# DDR3_LoongSon.net
KiCad netlist of a schematic drawn in Altium Designer
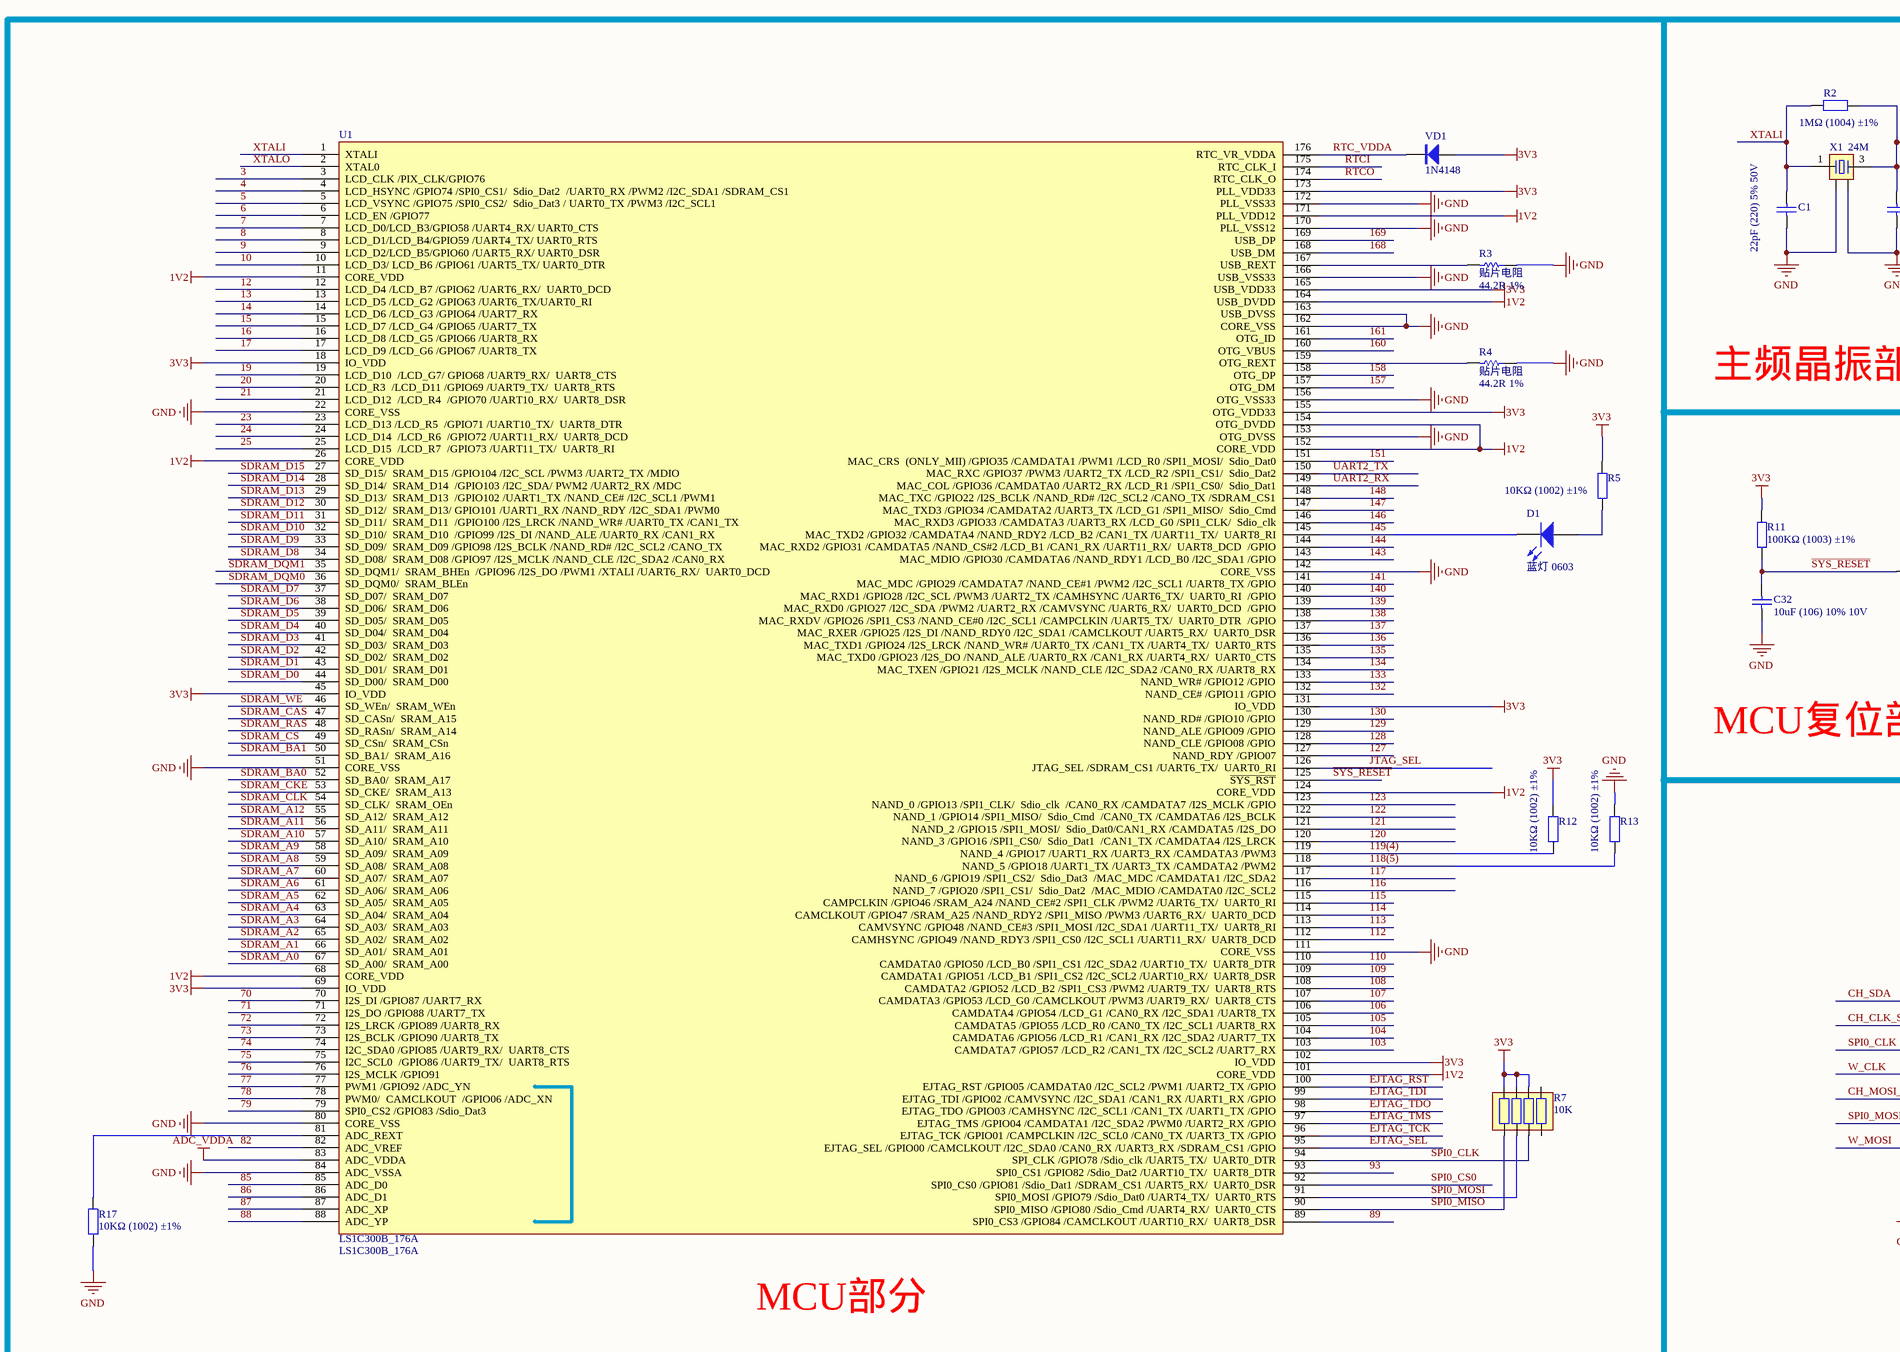
[diagram p0: DDR3_LoongSon.SchDoc, top left]
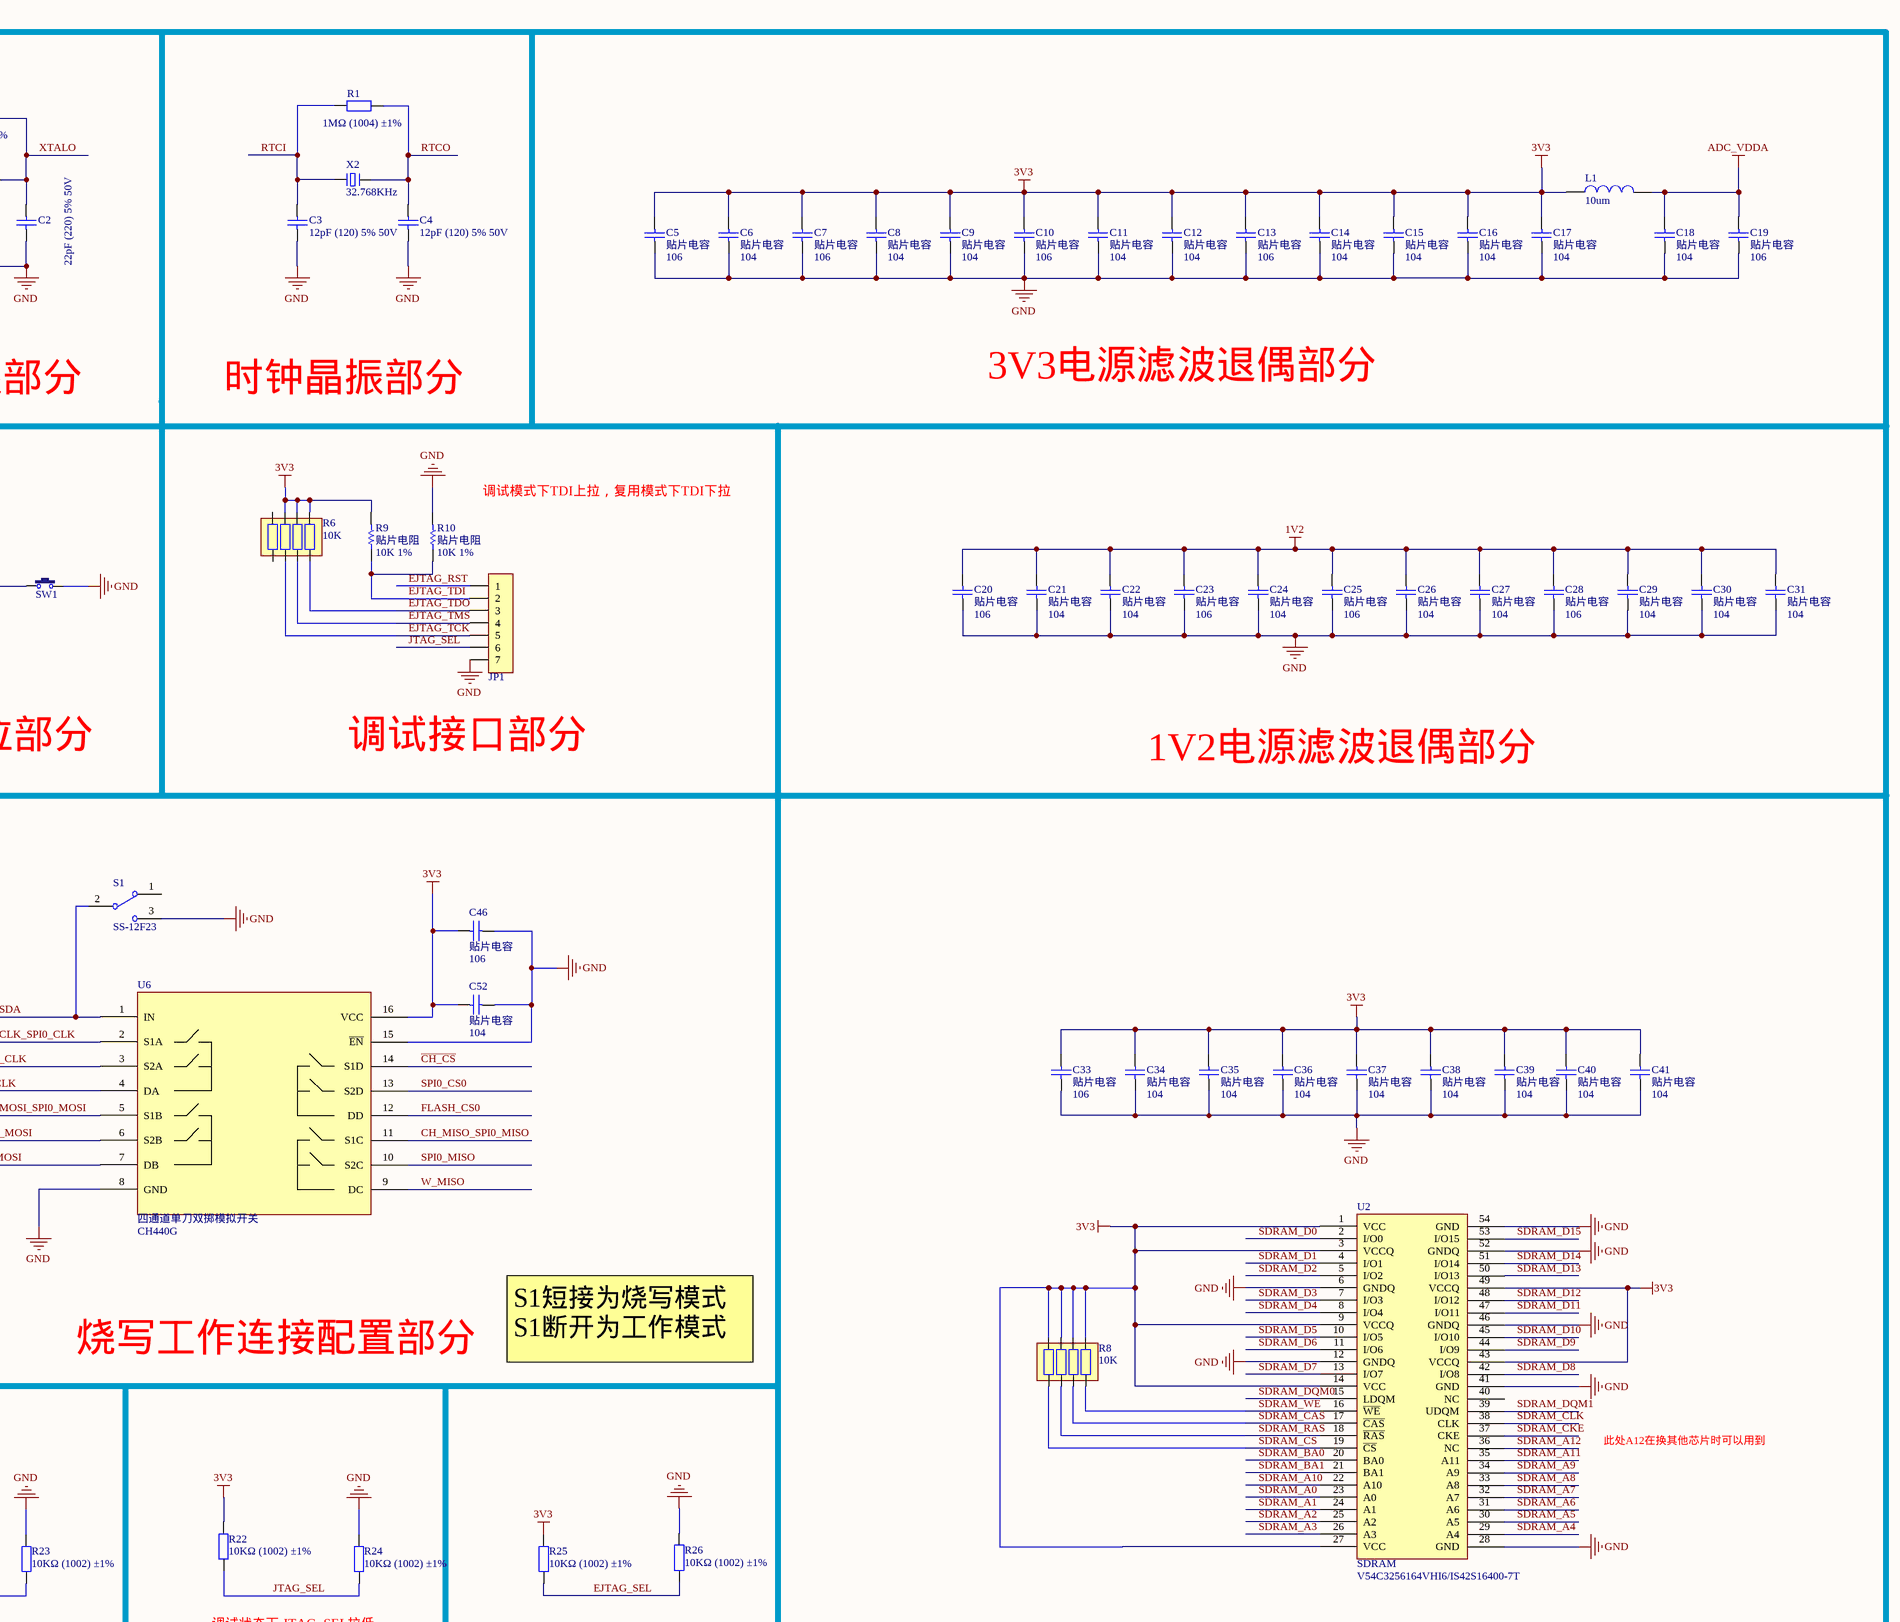
[diagram p1: DDR3_LoongSon.SchDoc, top right]
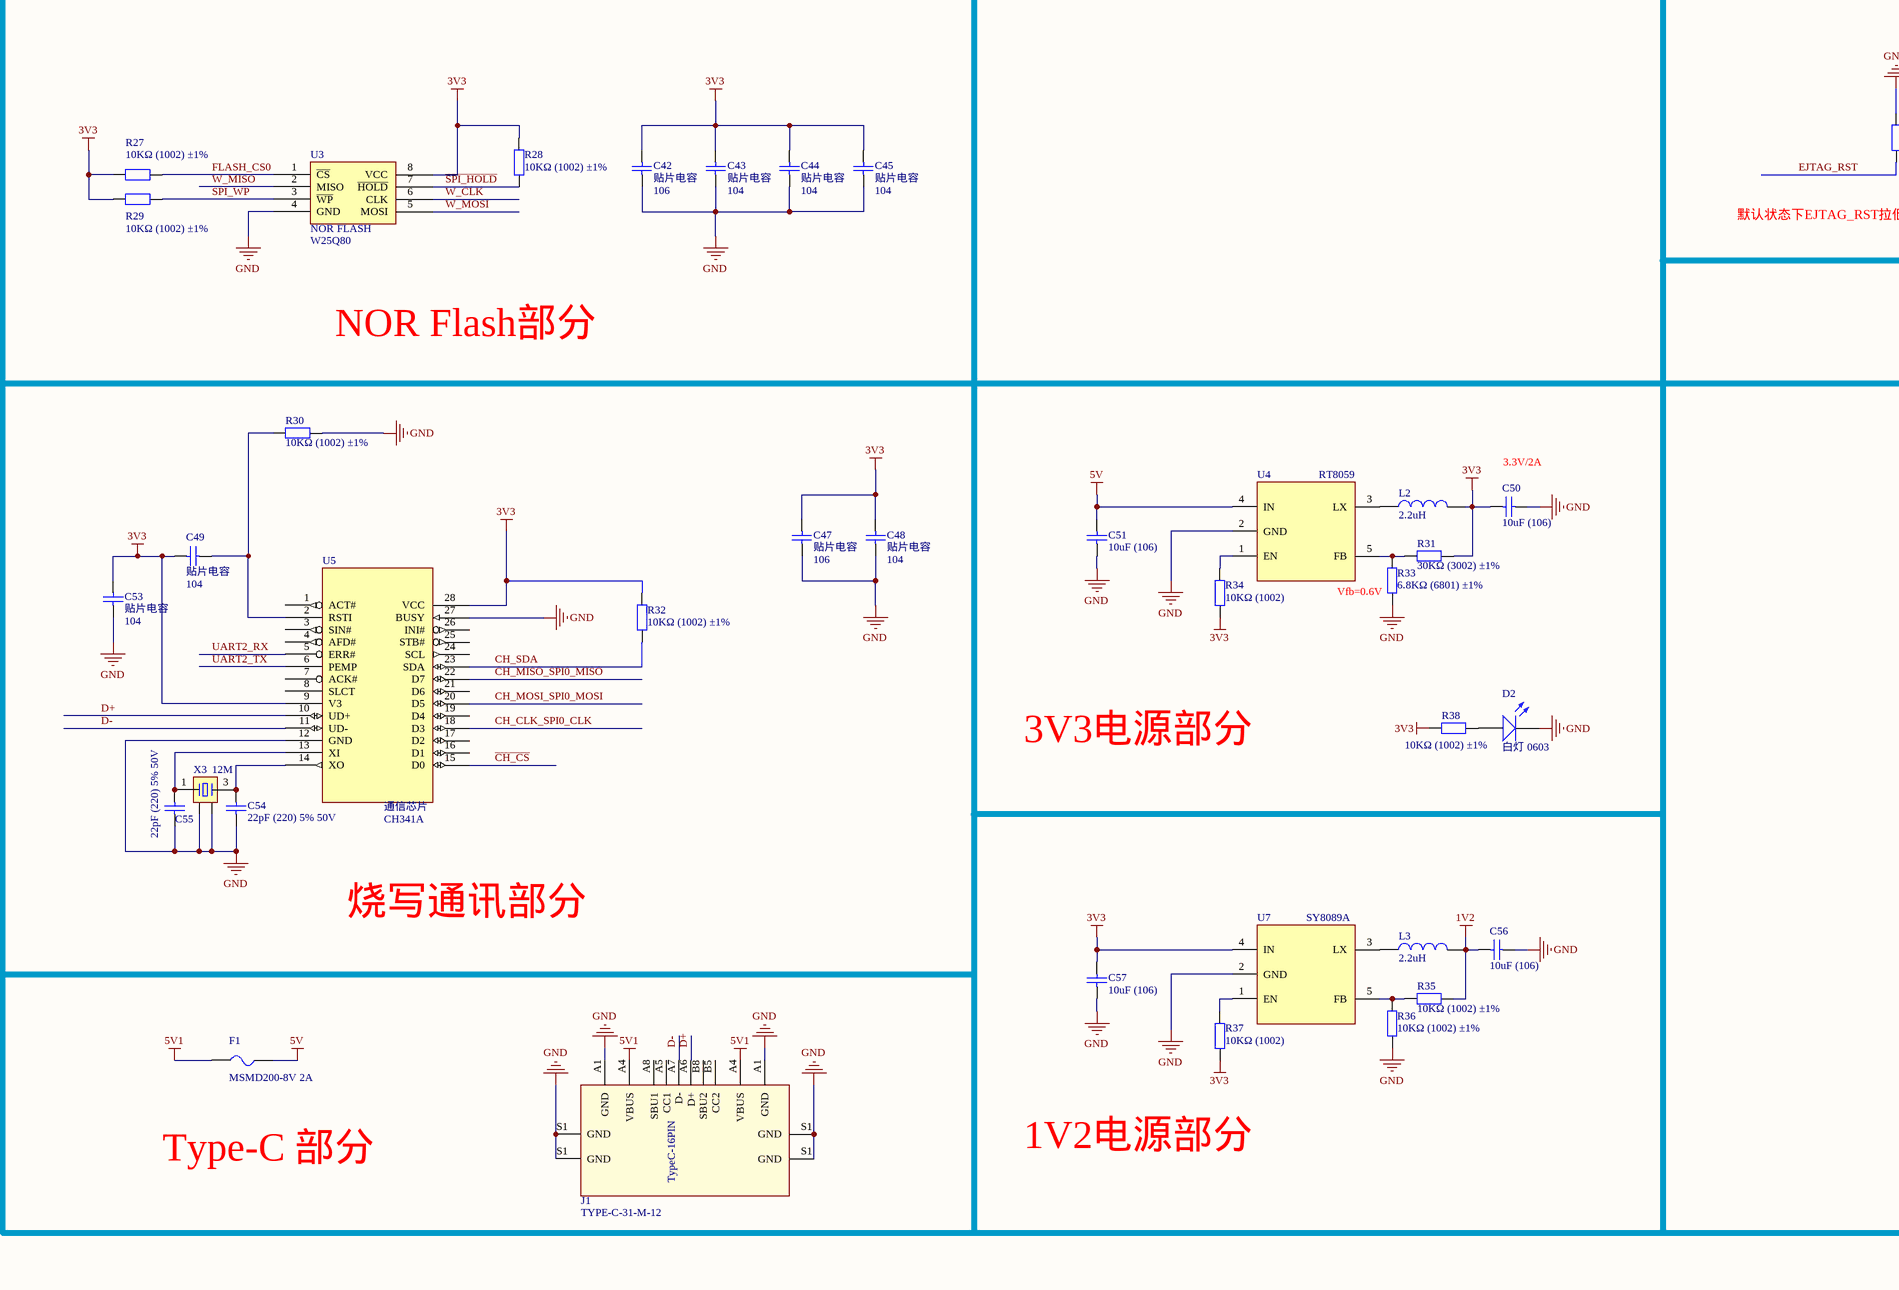
[diagram p2: DDR3_LoongSon.SchDoc, bottom left]
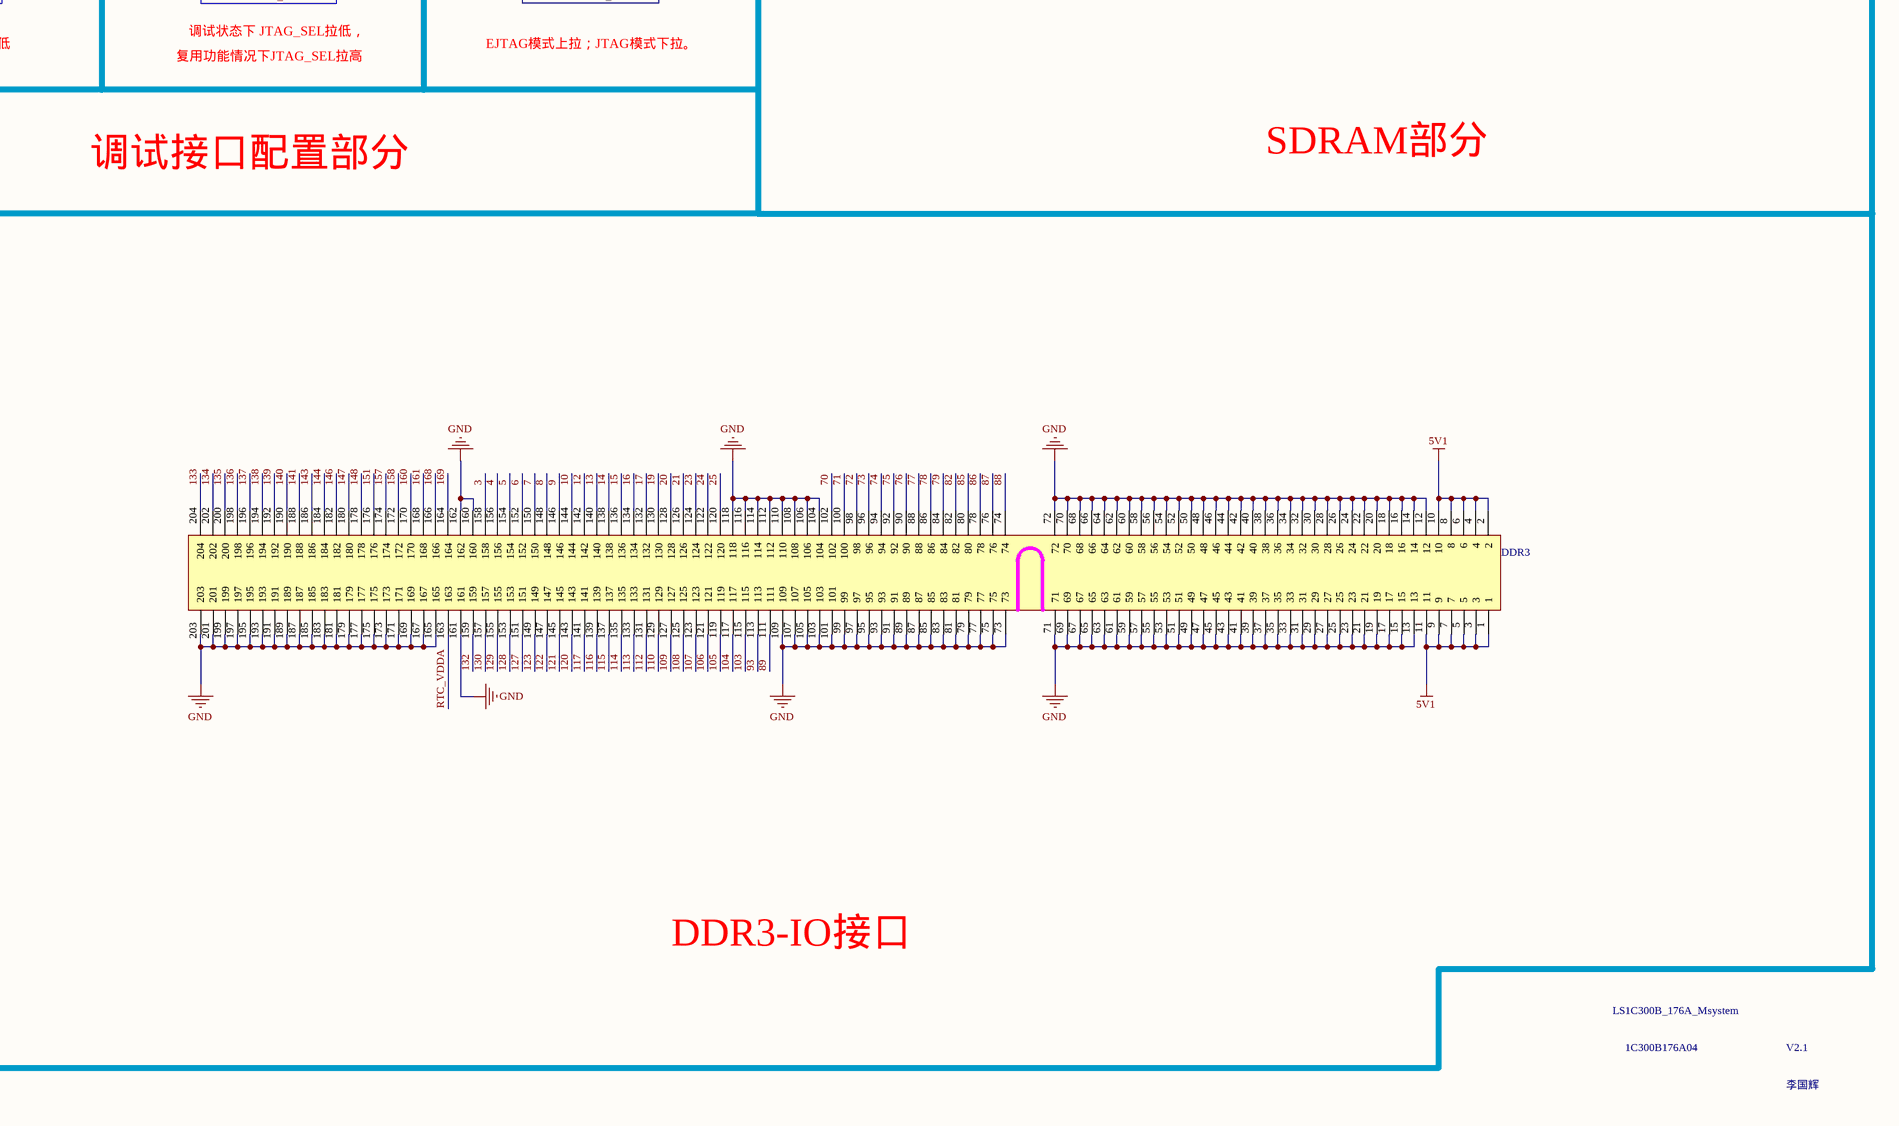
[diagram p3: DDR3_LoongSon.SchDoc, bottom right]

(export (version "E")
  (design (tool "Eeschema 10.0.6"))
  (components
    (comp (ref "C1")
      (value "22pF (220) 5% 50V")
      (footprint "LC-0603_C")
      (description "贴片电容")
      (libsource (lib "Miscellaneous Devices LC") (part "0603 22pF (220) 5% 50V"))
    )
    (comp (ref "C2")
      (value "22pF (220) 5% 50V")
      (footprint "LC-0603_C")
      (description "贴片电容")
      (libsource (lib "Miscellaneous Devices LC") (part "0603 22pF (220) 5% 50V"))
    )
    (comp (ref "C3")
      (value "12pF (120) 5% 50V")
      (footprint "LC-0603_C")
      (description "贴片电容")
      (libsource (lib "Miscellaneous Devices LC") (part "0603 12pF (120) 5% 50V"))
    )
    (comp (ref "C4")
      (value "12pF (120) 5% 50V")
      (footprint "LC-0603_C")
      (description "贴片电容")
      (libsource (lib "Miscellaneous Devices LC") (part "0603 12pF (120) 5% 50V"))
    )
    (comp (ref "C5")
      (value "贴片电容")
      (footprint "LC-0603_C")
      (description "Capacitor")
      (fields (field (name "ALTIUM_VALUE") "106") (field (name "PUBLISHER") "Altium Limited"))
      (libsource (lib "Miscellaneous Devices") (part "Cap"))
    )
    (comp (ref "C6")
      (value "贴片电容")
      (footprint "LC-0603_C")
      (description "Capacitor")
      (fields (field (name "ALTIUM_VALUE") "104") (field (name "PUBLISHER") "Altium Limited"))
      (libsource (lib "Miscellaneous Devices") (part "Cap"))
    )
    (comp (ref "C7")
      (value "贴片电容")
      (footprint "LC-0603_C")
      (description "Capacitor")
      (fields (field (name "ALTIUM_VALUE") "106") (field (name "PUBLISHER") "Altium Limited"))
      (libsource (lib "Miscellaneous Devices") (part "Cap"))
    )
    (comp (ref "C8")
      (value "贴片电容")
      (footprint "LC-0603_C")
      (description "Capacitor")
      (fields (field (name "ALTIUM_VALUE") "104") (field (name "PUBLISHER") "Altium Limited"))
      (libsource (lib "Miscellaneous Devices") (part "Cap"))
    )
    (comp (ref "C9")
      (value "贴片电容")
      (footprint "LC-0603_C")
      (description "Capacitor")
      (fields (field (name "ALTIUM_VALUE") "104") (field (name "PUBLISHER") "Altium Limited"))
      (libsource (lib "Miscellaneous Devices") (part "Cap"))
    )
    (comp (ref "C10")
      (value "贴片电容")
      (footprint "LC-0603_C")
      (description "Capacitor")
      (fields (field (name "ALTIUM_VALUE") "106") (field (name "PUBLISHER") "Altium Limited"))
      (libsource (lib "Miscellaneous Devices") (part "Cap"))
    )
    (comp (ref "C11")
      (value "贴片电容")
      (footprint "LC-0603_C")
      (description "Capacitor")
      (fields (field (name "ALTIUM_VALUE") "104") (field (name "PUBLISHER") "Altium Limited"))
      (libsource (lib "Miscellaneous Devices") (part "Cap"))
    )
    (comp (ref "C12")
      (value "贴片电容")
      (footprint "LC-0603_C")
      (description "Capacitor")
      (fields (field (name "ALTIUM_VALUE") "104") (field (name "PUBLISHER") "Altium Limited"))
      (libsource (lib "Miscellaneous Devices") (part "Cap"))
    )
    (comp (ref "C13")
      (value "贴片电容")
      (footprint "LC-0603_C")
      (description "Capacitor")
      (fields (field (name "ALTIUM_VALUE") "106") (field (name "PUBLISHER") "Altium Limited"))
      (libsource (lib "Miscellaneous Devices") (part "Cap"))
    )
    (comp (ref "C14")
      (value "贴片电容")
      (footprint "LC-0603_C")
      (description "Capacitor")
      (fields (field (name "ALTIUM_VALUE") "104") (field (name "PUBLISHER") "Altium Limited"))
      (libsource (lib "Miscellaneous Devices") (part "Cap"))
    )
    (comp (ref "C15")
      (value "贴片电容")
      (footprint "LC-0603_C")
      (description "Capacitor")
      (fields (field (name "ALTIUM_VALUE") "104") (field (name "PUBLISHER") "Altium Limited"))
      (libsource (lib "Miscellaneous Devices") (part "Cap"))
    )
    (comp (ref "C16")
      (value "贴片电容")
      (footprint "LC-0603_C")
      (description "Capacitor")
      (fields (field (name "ALTIUM_VALUE") "104") (field (name "PUBLISHER") "Altium Limited"))
      (libsource (lib "Miscellaneous Devices") (part "Cap"))
    )
    (comp (ref "C17")
      (value "贴片电容")
      (footprint "LC-0603_C")
      (description "Capacitor")
      (fields (field (name "ALTIUM_VALUE") "104") (field (name "PUBLISHER") "Altium Limited"))
      (libsource (lib "Miscellaneous Devices") (part "Cap"))
    )
    (comp (ref "C18")
      (value "贴片电容")
      (footprint "LC-0603_C")
      (description "Capacitor")
      (fields (field (name "ALTIUM_VALUE") "104") (field (name "PUBLISHER") "Altium Limited"))
      (libsource (lib "Miscellaneous Devices") (part "Cap"))
    )
    (comp (ref "C19")
      (value "贴片电容")
      (footprint "LC-0603_C")
      (description "Capacitor")
      (fields (field (name "ALTIUM_VALUE") "106") (field (name "PUBLISHER") "Altium Limited"))
      (libsource (lib "Miscellaneous Devices") (part "Cap"))
    )
    (comp (ref "C20")
      (value "贴片电容")
      (footprint "LC-0603_C")
      (description "Capacitor")
      (fields (field (name "ALTIUM_VALUE") "106") (field (name "PUBLISHER") "Altium Limited"))
      (libsource (lib "Miscellaneous Devices") (part "Cap"))
    )
    (comp (ref "C21")
      (value "贴片电容")
      (footprint "LC-0603_C")
      (description "Capacitor")
      (fields (field (name "ALTIUM_VALUE") "104") (field (name "PUBLISHER") "Altium Limited"))
      (libsource (lib "Miscellaneous Devices") (part "Cap"))
    )
    (comp (ref "C22")
      (value "贴片电容")
      (footprint "LC-0603_C")
      (description "Capacitor")
      (fields (field (name "ALTIUM_VALUE") "104") (field (name "PUBLISHER") "Altium Limited"))
      (libsource (lib "Miscellaneous Devices") (part "Cap"))
    )
    (comp (ref "C23")
      (value "贴片电容")
      (footprint "LC-0603_C")
      (description "Capacitor")
      (fields (field (name "ALTIUM_VALUE") "106") (field (name "PUBLISHER") "Altium Limited"))
      (libsource (lib "Miscellaneous Devices") (part "Cap"))
    )
    (comp (ref "C24")
      (value "贴片电容")
      (footprint "LC-0603_C")
      (description "Capacitor")
      (fields (field (name "ALTIUM_VALUE") "104") (field (name "PUBLISHER") "Altium Limited"))
      (libsource (lib "Miscellaneous Devices") (part "Cap"))
    )
    (comp (ref "C25")
      (value "贴片电容")
      (footprint "LC-0603_C")
      (description "Capacitor")
      (fields (field (name "ALTIUM_VALUE") "106") (field (name "PUBLISHER") "Altium Limited"))
      (libsource (lib "Miscellaneous Devices") (part "Cap"))
    )
    (comp (ref "C26")
      (value "贴片电容")
      (footprint "LC-0603_C")
      (description "Capacitor")
      (fields (field (name "ALTIUM_VALUE") "104") (field (name "PUBLISHER") "Altium Limited"))
      (libsource (lib "Miscellaneous Devices") (part "Cap"))
    )
    (comp (ref "C27")
      (value "贴片电容")
      (footprint "LC-0603_C")
      (description "Capacitor")
      (fields (field (name "ALTIUM_VALUE") "104") (field (name "PUBLISHER") "Altium Limited"))
      (libsource (lib "Miscellaneous Devices") (part "Cap"))
    )
    (comp (ref "C28")
      (value "贴片电容")
      (footprint "LC-0603_C")
      (description "Capacitor")
      (fields (field (name "ALTIUM_VALUE") "106") (field (name "PUBLISHER") "Altium Limited"))
      (libsource (lib "Miscellaneous Devices") (part "Cap"))
    )
    (comp (ref "C29")
      (value "贴片电容")
      (footprint "LC-0603_C")
      (description "Capacitor")
      (fields (field (name "ALTIUM_VALUE") "104") (field (name "PUBLISHER") "Altium Limited"))
      (libsource (lib "Miscellaneous Devices") (part "Cap"))
    )
    (comp (ref "C30")
      (value "贴片电容")
      (footprint "LC-0603_C")
      (description "Capacitor")
      (fields (field (name "ALTIUM_VALUE") "104") (field (name "PUBLISHER") "Altium Limited"))
      (libsource (lib "Miscellaneous Devices") (part "Cap"))
    )
    (comp (ref "C31")
      (value "贴片电容")
      (footprint "LC-0603_C")
      (description "Capacitor")
      (fields (field (name "ALTIUM_VALUE") "104") (field (name "PUBLISHER") "Altium Limited"))
      (libsource (lib "Miscellaneous Devices") (part "Cap"))
    )
    (comp (ref "C32")
      (value "10uF (106) 10% 10V")
      (footprint "LC-0603_C")
      (description "贴片电容")
      (libsource (lib "Miscellaneous Devices LC") (part "0603 10uF (106) 10% 10V"))
    )
    (comp (ref "C33")
      (value "贴片电容")
      (footprint "LC-0603_C")
      (description "Capacitor")
      (fields (field (name "ALTIUM_VALUE") "106") (field (name "PUBLISHER") "Altium Limited"))
      (libsource (lib "Miscellaneous Devices") (part "Cap"))
    )
    (comp (ref "C34")
      (value "贴片电容")
      (footprint "LC-0603_C")
      (description "Capacitor")
      (fields (field (name "ALTIUM_VALUE") "104") (field (name "PUBLISHER") "Altium Limited"))
      (libsource (lib "Miscellaneous Devices") (part "Cap"))
    )
    (comp (ref "C35")
      (value "贴片电容")
      (footprint "LC-0603_C")
      (description "Capacitor")
      (fields (field (name "ALTIUM_VALUE") "104") (field (name "PUBLISHER") "Altium Limited"))
      (libsource (lib "Miscellaneous Devices") (part "Cap"))
    )
    (comp (ref "C36")
      (value "贴片电容")
      (footprint "LC-0603_C")
      (description "Capacitor")
      (fields (field (name "ALTIUM_VALUE") "104") (field (name "PUBLISHER") "Altium Limited"))
      (libsource (lib "Miscellaneous Devices") (part "Cap"))
    )
    (comp (ref "C37")
      (value "贴片电容")
      (footprint "LC-0603_C")
      (description "Capacitor")
      (fields (field (name "ALTIUM_VALUE") "104") (field (name "PUBLISHER") "Altium Limited"))
      (libsource (lib "Miscellaneous Devices") (part "Cap"))
    )
    (comp (ref "C38")
      (value "贴片电容")
      (footprint "LC-0603_C")
      (description "Capacitor")
      (fields (field (name "ALTIUM_VALUE") "104") (field (name "PUBLISHER") "Altium Limited"))
      (libsource (lib "Miscellaneous Devices") (part "Cap"))
    )
    (comp (ref "C39")
      (value "贴片电容")
      (footprint "LC-0603_C")
      (description "Capacitor")
      (fields (field (name "ALTIUM_VALUE") "104") (field (name "PUBLISHER") "Altium Limited"))
      (libsource (lib "Miscellaneous Devices") (part "Cap"))
    )
    (comp (ref "C40")
      (value "贴片电容")
      (footprint "LC-0603_C")
      (description "Capacitor")
      (fields (field (name "ALTIUM_VALUE") "104") (field (name "PUBLISHER") "Altium Limited"))
      (libsource (lib "Miscellaneous Devices") (part "Cap"))
    )
    (comp (ref "C41")
      (value "贴片电容")
      (footprint "LC-0603_C")
      (description "Capacitor")
      (fields (field (name "ALTIUM_VALUE") "104") (field (name "PUBLISHER") "Altium Limited"))
      (libsource (lib "Miscellaneous Devices") (part "Cap"))
    )
    (comp (ref "C42")
      (value "贴片电容")
      (footprint "LC-0603_C")
      (description "Capacitor")
      (fields (field (name "ALTIUM_VALUE") "106") (field (name "PUBLISHER") "Altium Limited"))
      (libsource (lib "Miscellaneous Devices") (part "Cap"))
    )
    (comp (ref "C43")
      (value "贴片电容")
      (footprint "LC-0603_C")
      (description "Capacitor")
      (fields (field (name "ALTIUM_VALUE") "104") (field (name "PUBLISHER") "Altium Limited"))
      (libsource (lib "Miscellaneous Devices") (part "Cap"))
    )
    (comp (ref "C44")
      (value "贴片电容")
      (footprint "LC-0603_C")
      (description "Capacitor")
      (fields (field (name "ALTIUM_VALUE") "104") (field (name "PUBLISHER") "Altium Limited"))
      (libsource (lib "Miscellaneous Devices") (part "Cap"))
    )
    (comp (ref "C45")
      (value "贴片电容")
      (footprint "LC-0603_C")
      (description "Capacitor")
      (fields (field (name "ALTIUM_VALUE") "104") (field (name "PUBLISHER") "Altium Limited"))
      (libsource (lib "Miscellaneous Devices") (part "Cap"))
    )
    (comp (ref "C46")
      (value "贴片电容")
      (footprint "LC-0603_C")
      (description "Capacitor")
      (fields (field (name "ALTIUM_VALUE") "106") (field (name "PUBLISHER") "Altium Limited"))
      (libsource (lib "Miscellaneous Devices") (part "Cap"))
    )
    (comp (ref "C47")
      (value "贴片电容")
      (footprint "LC-0603_C")
      (description "Capacitor")
      (fields (field (name "ALTIUM_VALUE") "106") (field (name "PUBLISHER") "Altium Limited"))
      (libsource (lib "Miscellaneous Devices") (part "Cap"))
    )
    (comp (ref "C48")
      (value "贴片电容")
      (footprint "LC-0603_C")
      (description "Capacitor")
      (fields (field (name "ALTIUM_VALUE") "104") (field (name "PUBLISHER") "Altium Limited"))
      (libsource (lib "Miscellaneous Devices") (part "Cap"))
    )
    (comp (ref "C49")
      (value "贴片电容")
      (footprint "LC-0603_C")
      (description "Capacitor")
      (fields (field (name "ALTIUM_VALUE") "104") (field (name "PUBLISHER") "Altium Limited"))
      (libsource (lib "Miscellaneous Devices") (part "Cap"))
    )
    (comp (ref "C50")
      (value "10uF (106)")
      (footprint "LC-0603_C")
      (description "贴片电容")
      (libsource (lib "Miscellaneous Devices LC") (part "0603 10uF (106) 10% 10V"))
    )
    (comp (ref "C51")
      (value "10uF (106)")
      (footprint "LC-0603_C")
      (description "贴片电容")
      (libsource (lib "Miscellaneous Devices LC") (part "0603 10uF (106) 10% 10V"))
    )
    (comp (ref "C52")
      (value "贴片电容")
      (footprint "LC-0603_C")
      (description "Capacitor")
      (fields (field (name "ALTIUM_VALUE") "104") (field (name "PUBLISHER") "Altium Limited"))
      (libsource (lib "Miscellaneous Devices") (part "Cap"))
    )
    (comp (ref "C53")
      (value "贴片电容")
      (footprint "LC-0603_C")
      (description "Capacitor")
      (fields (field (name "ALTIUM_VALUE") "104") (field (name "PUBLISHER") "Altium Limited"))
      (libsource (lib "Miscellaneous Devices") (part "Cap"))
    )
    (comp (ref "C54")
      (value "22pF (220) 5% 50V")
      (footprint "LC-0603_C")
      (description "贴片电容")
      (libsource (lib "Miscellaneous Devices LC") (part "0603 22pF (220) 5% 50V"))
    )
    (comp (ref "C55")
      (value "22pF (220) 5% 50V")
      (footprint "LC-0603_C")
      (description "贴片电容")
      (libsource (lib "Miscellaneous Devices LC") (part "0603 22pF (220) 5% 50V"))
    )
    (comp (ref "C56")
      (value "10uF (106)")
      (footprint "LC-0603_C")
      (description "贴片电容")
      (libsource (lib "Miscellaneous Devices LC") (part "0603 10uF (106) 10% 10V"))
    )
    (comp (ref "C57")
      (value "10uF (106)")
      (footprint "LC-0603_C")
      (description "贴片电容")
      (libsource (lib "Miscellaneous Devices LC") (part "0603 10uF (106) 10% 10V"))
    )
    (comp (ref "D1")
      (value "蓝灯 0603")
      (footprint "LC-0603_LED_S1")
      (description "发光二极管")
      (libsource (lib "Miscellaneous Devices LC") (part "0603 蓝灯"))
    )
    (comp (ref "D2")
      (value "白灯 0603")
      (footprint "LC-0603_LED_S1")
      (description "发光二极管")
      (libsource (lib "Miscellaneous Devices LC") (part "0603 白灯"))
    )
    (comp (ref "DDR1") (value "DDR3") (footprint "DDR3_PLUG_R") (libsource (lib "Type-C") (part "DDR3")))
    (comp (ref "F1")
      (value "MSMD200-8V 2A")
      (footprint "FU 1206")
      (description "贴片保险丝")
      (fields (field (name "版权归属") "源创客"))
      (libsource (lib "保险丝-晶振") (part "FU"))
    )
    (comp (ref "J1")
      (value "TYPE-C-31-M-12")
      (footprint "TYPE-C-31-M-12")
      (libsource (lib "Type-C") (part "TYPE-C-31-M-12"))
    )
    (comp (ref "JP1")
      (value "HDR-1X7")
      (footprint "HDR-1X7")
      (description "7P接插件")
      (fields (field (name "版权归属") "源创客"))
      (libsource (lib "接插件") (part "Header 7"))
    )
    (comp (ref "L1")
      (value "10um")
      (footprint "L 0603")
      (description "小功率贴片电感")
      (fields (field (name "版权归属") "源创客"))
      (libsource (lib "电阻-电容-电感") (part "L"))
    )
    (comp (ref "L2")
      (value "2.2uH")
      (footprint "2520-L")
      (description "小功率贴片电感")
      (fields (field (name "版权归属") "源创客"))
      (libsource (lib "电阻-电容-电感") (part "L"))
    )
    (comp (ref "L3")
      (value "2.2uH")
      (footprint "2520-L")
      (description "小功率贴片电感")
      (fields (field (name "版权归属") "源创客"))
      (libsource (lib "电阻-电容-电感") (part "L"))
    )
    (comp (ref "R1")
      (value "1MΩ (1004) ±1%")
      (footprint "LC-0603_R")
      (description "贴片电阻")
      (libsource (lib "Miscellaneous Devices LC") (part "0603 1MΩ (1004) 1%"))
    )
    (comp (ref "R2")
      (value "1MΩ (1004) ±1%")
      (footprint "LC-0603_R")
      (description "贴片电阻")
      (libsource (lib "Miscellaneous Devices LC") (part "0603 1MΩ (1004) 1%"))
    )
    (comp (ref "R3")
      (value "贴片电阻")
      (footprint "LC-0603_R")
      (description "Resistor")
      (fields (field (name "ALTIUM_VALUE") "44.2R 1%") (field (name "PUBLISHER") "Altium Limited"))
      (libsource (lib "Miscellaneous Devices") (part "Res1"))
    )
    (comp (ref "R4")
      (value "贴片电阻")
      (footprint "LC-0603_R")
      (description "Resistor")
      (fields (field (name "ALTIUM_VALUE") "44.2R 1%") (field (name "PUBLISHER") "Altium Limited"))
      (libsource (lib "Miscellaneous Devices") (part "Res1"))
    )
    (comp (ref "R5")
      (value "10KΩ (1002) ±1%")
      (footprint "LC-0603_R")
      (description "贴片电阻")
      (libsource (lib "Miscellaneous Devices LC") (part "0603 10KΩ (1002) 1%"))
    )
    (comp (ref "R6")
      (value "10K")
      (footprint "RCA-8P4R-0603")
      (description "贴片网络排阻")
      (fields (field (name "版权归属") "源创客"))
      (libsource (lib "电阻-电容-电感") (part "R-8P4R"))
    )
    (comp (ref "R7")
      (value "10K")
      (footprint "RCA-8P4R-0603")
      (description "贴片网络排阻")
      (fields (field (name "版权归属") "源创客"))
      (libsource (lib "电阻-电容-电感") (part "R-8P4R"))
    )
    (comp (ref "R8")
      (value "10K")
      (footprint "RCA-8P4R-0603")
      (description "贴片网络排阻")
      (fields (field (name "版权归属") "源创客"))
      (libsource (lib "电阻-电容-电感") (part "R-8P4R"))
    )
    (comp (ref "R9")
      (value "贴片电阻")
      (footprint "LC-0603_R")
      (description "Resistor")
      (fields (field (name "ALTIUM_VALUE") "10K 1%") (field (name "PUBLISHER") "Altium Limited"))
      (libsource (lib "Miscellaneous Devices") (part "Res1"))
    )
    (comp (ref "R10")
      (value "贴片电阻")
      (footprint "LC-0603_R")
      (description "Resistor")
      (fields (field (name "ALTIUM_VALUE") "10K 1%") (field (name "PUBLISHER") "Altium Limited"))
      (libsource (lib "Miscellaneous Devices") (part "Res1"))
    )
    (comp (ref "R11")
      (value "100KΩ (1003) ±1%")
      (footprint "LC-0603_R")
      (description "贴片电阻")
      (libsource (lib "Miscellaneous Devices LC") (part "0603 100KΩ (1003) 1%"))
    )
    (comp (ref "R12")
      (value "10KΩ (1002) ±1%")
      (footprint "LC-0603_R")
      (description "贴片电阻")
      (libsource (lib "Miscellaneous Devices LC") (part "0603 10KΩ (1002) 1%"))
    )
    (comp (ref "R13")
      (value "10KΩ (1002) ±1%")
      (footprint "LC-0603_R")
      (description "贴片电阻")
      (libsource (lib "Miscellaneous Devices LC") (part "0603 10KΩ (1002) 1%"))
    )
    (comp (ref "R17")
      (value "10KΩ (1002) ±1%")
      (footprint "LC-0603_R")
      (description "贴片电阻")
      (libsource (lib "Miscellaneous Devices LC") (part "0603 10KΩ (1002) 1%"))
    )
    (comp (ref "R22")
      (value "10KΩ (1002) ±1%")
      (footprint "LC-0603_R")
      (description "贴片电阻")
      (libsource (lib "Miscellaneous Devices LC") (part "0603 10KΩ (1002) 1%"))
    )
    (comp (ref "R23")
      (value "10KΩ (1002) ±1%")
      (footprint "LC-0603_R")
      (description "贴片电阻")
      (libsource (lib "Miscellaneous Devices LC") (part "0603 10KΩ (1002) 1%"))
    )
    (comp (ref "R24")
      (value "10KΩ (1002) ±1%")
      (footprint "LC-0603_R")
      (description "贴片电阻")
      (libsource (lib "Miscellaneous Devices LC") (part "0603 10KΩ (1002) 1%"))
    )
    (comp (ref "R25")
      (value "10KΩ (1002) ±1%")
      (footprint "LC-0603_R")
      (description "贴片电阻")
      (libsource (lib "Miscellaneous Devices LC") (part "0603 10KΩ (1002) 1%"))
    )
    (comp (ref "R26")
      (value "10KΩ (1002) ±1%")
      (footprint "LC-0603_R")
      (description "贴片电阻")
      (libsource (lib "Miscellaneous Devices LC") (part "0603 10KΩ (1002) 1%"))
    )
    (comp (ref "R27")
      (value "10KΩ (1002) ±1%")
      (footprint "LC-0603_R")
      (description "贴片电阻")
      (libsource (lib "") (part "0603 10KΩ (1002) 1%_1"))
    )
    (comp (ref "R28")
      (value "10KΩ (1002) ±1%")
      (footprint "LC-0603_R")
      (description "贴片电阻")
      (libsource (lib "Miscellaneous Devices LC") (part "0603 10KΩ (1002) 1%"))
    )
    (comp (ref "R29")
      (value "10KΩ (1002) ±1%")
      (footprint "LC-0603_R")
      (description "贴片电阻")
      (libsource (lib "") (part "0603 10KΩ (1002) 1%_1"))
    )
    (comp (ref "R30")
      (value "10KΩ (1002) ±1%")
      (footprint "LC-0603_R")
      (description "贴片电阻")
      (libsource (lib "") (part "0603 10KΩ (1002) 1%_1"))
    )
    (comp (ref "R31")
      (value "30KΩ (3002) ±1%")
      (footprint "LC-0603_R")
      (description "贴片电阻")
      (libsource (lib "Miscellaneous Devices LC") (part "0603 30KΩ (3002) 1%"))
    )
    (comp (ref "R32")
      (value "10KΩ (1002) ±1%")
      (footprint "LC-0603_R")
      (description "贴片电阻")
      (libsource (lib "Miscellaneous Devices LC") (part "0603 10KΩ (1002) 1%"))
    )
    (comp (ref "R33")
      (value "6.8KΩ (6801) ±1%")
      (footprint "LC-0603_R")
      (description "贴片电阻")
      (libsource (lib "Miscellaneous Devices LC") (part "0603 6.8KΩ (6801) 1%"))
    )
    (comp (ref "R34")
      (value "10KΩ (1002)")
      (footprint "LC-0603_R")
      (description "贴片电阻")
      (libsource (lib "Miscellaneous Devices LC") (part "0603 10KΩ (1002) 1%"))
    )
    (comp (ref "R35")
      (value "10KΩ (1002) ±1%")
      (footprint "LC-0603_R")
      (description "贴片电阻")
      (libsource (lib "") (part "0603 10KΩ (1002) 1%_1"))
    )
    (comp (ref "R36")
      (value "10KΩ (1002) ±1%")
      (footprint "LC-0603_R")
      (description "贴片电阻")
      (libsource (lib "Miscellaneous Devices LC") (part "0603 10KΩ (1002) 1%"))
    )
    (comp (ref "R37")
      (value "10KΩ (1002)")
      (footprint "LC-0603_R")
      (description "贴片电阻")
      (libsource (lib "Miscellaneous Devices LC") (part "0603 10KΩ (1002) 1%"))
    )
    (comp (ref "R38")
      (value "10KΩ (1002) ±1%")
      (footprint "LC-0603_R")
      (description "贴片电阻")
      (libsource (lib "") (part "0603 10KΩ (1002) 1%_1"))
    )
    (comp (ref "S1")
      (value "SS-12F23")
      (footprint "MSK-12C01-07")
      (description "1路波动开关")
      (fields (field (name "版权归属") "源创客"))
      (libsource (lib "按键-开关") (part "SSW-1P"))
    )
    (comp (ref "SW1")
      (value "3x6x5")
      (footprint "TSW SMD-3*6*2.5")
      (description "3x6轻触开关")
      (fields (field (name "版权归属") "源创客"))
      (libsource (lib "按键-开关") (part "TSW 3x6"))
    )
    (comp (ref "U1")
      (value "LS1C300B_176A")
      (footprint "QFP176")
      (description "龙芯1C300B QFP176A")
      (fields (field (name "ALTIUM_VALUE") "LS1C300B_176A"))
      (libsource (lib "Type-C") (part "LS1C300B_176A"))
    )
    (comp (ref "U2")
      (value "SDRAM")
      (footprint "TSOP54")
      (description "ISSI 公司SDRAM ， 166, 133, 100 MHz")
      (fields (field (name "ALTIUM_VALUE") "V54C3256164VHI6/IS42S16400-7T"))
      (libsource (lib "Type-C") (part "IS42S16400"))
    )
    (comp (ref "U3")
      (value "NOR FLASH")
      (footprint "SOIC-8-N")
      (description "nor flash W25Q64....华邦")
      (fields (field (name "ALTIUM_VALUE") "W25Q80"))
      (libsource (lib "Type-C") (part "W25Q80BV"))
    )
    (comp (ref "U4")
      (value "RT8059")
      (footprint "SOT23-5N")
      (description "LDO")
      (libsource (lib "Type-C") (part "RT8059"))
    )
    (comp (ref "U5")
      (value "通信芯片")
      (footprint "SOP28")
      (description "USB to Print Port / Parallel")
      (fields (field (name "ALTIUM_VALUE") "CH341A"))
      (libsource (lib "Type-C") (part "CH341A"))
    )
    (comp (ref "U6")
      (value "四通道单刀双掷模拟开关")
      (footprint "SOP-16")
      (description "四通道单刀双掷模拟开关 ，EN 低电平使能，IN 低电平 1#端导通，高电平2#端导通，DX是公共端")
      (fields (field (name "ALTIUM_VALUE") "CH440G"))
      (libsource (lib "LGHLIB") (part "CH440"))
    )
    (comp (ref "U7")
      (value "SY8089A")
      (footprint "SOT23-5N")
      (description "LDO")
      (libsource (lib "Type-C") (part "SY8089A"))
    )
    (comp (ref "VD1")
      (value "1N4148")
      (footprint "MINI_MELF (LL34)")
      (description "高速开关二极管")
      (fields (field (name "版权归属") "源创客"))
      (libsource (lib "二极管-整流桥") (part "1N4148"))
    )
    (comp (ref "X1")
      (value "24M")
      (footprint "XTAL-3225")
      (description "4脚晶振")
      (fields (field (name "版权归属") "源创客"))
      (libsource (lib "保险丝-晶振") (part "XTAL-4"))
    )
    (comp (ref "X2")
      (value "32.768KHz")
      (footprint "XTAL-3215")
      (description "2脚晶振")
      (fields (field (name "版权归属") "源创客"))
      (libsource (lib "保险丝-晶振") (part "XTAL-2"))
    )
    (comp (ref "X3")
      (value "12M")
      (footprint "XTAL-3225")
      (description "4脚晶振")
      (fields (field (name "版权归属") "源创客"))
      (libsource (lib "保险丝-晶振") (part "XTAL-4"))
    )
  )
  (nets
    (net (code "1") (name "/3") (class "Default")
      (node (ref "DDR1") (pin "158") (pinfunction "158_158") (pintype "passive"))
      (node (ref "U1") (pin "3") (pinfunction "LCD_CLK_/PIX_CLK/GPIO76_3") (pintype "passive"))
    )
    (net (code "2") (name "/4") (class "Default")
      (node (ref "DDR1") (pin "156") (pinfunction "156_156") (pintype "passive"))
      (node (ref "U1") (pin "4") (pinfunction "LCD_HSYNC_/GPIO74_/SPI0_CS1/__Sdio_Dat2__/UART0_RX_/PWM2_/I2C_SDA1_/SDRAM_CS1_4") (pintype "passive"))
    )
    (net (code "3") (name "/5") (class "Default")
      (node (ref "DDR1") (pin "154") (pinfunction "154_154") (pintype "passive"))
      (node (ref "U1") (pin "5") (pinfunction "LCD_VSYNC_/GPIO75_/SPI0_CS2/__Sdio_Dat3_/_UART0_TX_/PWM3_/I2C_SCL1_5") (pintype "passive"))
    )
    (net (code "4") (name "/6") (class "Default")
      (node (ref "DDR1") (pin "152") (pinfunction "152_152") (pintype "passive"))
      (node (ref "U1") (pin "6") (pinfunction "LCD_EN_/GPIO77_6") (pintype "passive"))
    )
    (net (code "5") (name "/7") (class "Default")
      (node (ref "DDR1") (pin "150") (pinfunction "150_150") (pintype "passive"))
      (node (ref "U1") (pin "7") (pinfunction "LCD_D0/LCD_B3/GPIO58_/UART4_RX/_UART0_CTS_7") (pintype "passive"))
    )
    (net (code "6") (name "/8") (class "Default")
      (node (ref "DDR1") (pin "148") (pinfunction "148_148") (pintype "passive"))
      (node (ref "U1") (pin "8") (pinfunction "LCD_D1/LCD_B4/GPIO59_/UART4_TX/_UART0_RTS_8") (pintype "passive"))
    )
    (net (code "7") (name "/9") (class "Default")
      (node (ref "DDR1") (pin "146") (pinfunction "146_146") (pintype "passive"))
      (node (ref "U1") (pin "9") (pinfunction "LCD_D2/LCD_B5/GPIO60_/UART5_RX/_UART0_DSR_9") (pintype "passive"))
    )
    (net (code "8") (name "/10") (class "Default")
      (node (ref "DDR1") (pin "144") (pinfunction "144_144") (pintype "passive"))
      (node (ref "U1") (pin "10") (pinfunction "LCD_D3/_LCD_B6_/GPIO61_/UART5_TX/_UART0_DTR_10") (pintype "passive"))
    )
    (net (code "9") (name "/12") (class "Default")
      (node (ref "DDR1") (pin "142") (pinfunction "142_142") (pintype "passive"))
      (node (ref "U1") (pin "12") (pinfunction "LCD_D4_/LCD_B7_/GPIO62_/UART6_RX/__UART0_DCD_12") (pintype "passive"))
    )
    (net (code "10") (name "/13") (class "Default")
      (node (ref "DDR1") (pin "140") (pinfunction "140_140") (pintype "passive"))
      (node (ref "U1") (pin "13") (pinfunction "LCD_D5_/LCD_G2_/GPIO63_/UART6_TX/UART0_RI_13") (pintype "passive"))
    )
    (net (code "11") (name "/14") (class "Default")
      (node (ref "DDR1") (pin "138") (pinfunction "138_138") (pintype "passive"))
      (node (ref "U1") (pin "14") (pinfunction "LCD_D6_/LCD_G3_/GPIO64_/UART7_RX_14") (pintype "passive"))
    )
    (net (code "12") (name "/15") (class "Default")
      (node (ref "DDR1") (pin "136") (pinfunction "136_136") (pintype "passive"))
      (node (ref "U1") (pin "15") (pinfunction "LCD_D7_/LCD_G4_/GPIO65_/UART7_TX_15") (pintype "passive"))
    )
    (net (code "13") (name "/16") (class "Default")
      (node (ref "DDR1") (pin "134") (pinfunction "134_134") (pintype "passive"))
      (node (ref "U1") (pin "16") (pinfunction "LCD_D8_/LCD_G5_/GPIO66_/UART8_RX_16") (pintype "passive"))
    )
    (net (code "14") (name "/17") (class "Default")
      (node (ref "DDR1") (pin "132") (pinfunction "132_132") (pintype "passive"))
      (node (ref "U1") (pin "17") (pinfunction "LCD_D9_/LCD_G6_/GPIO67_/UART8_TX_17") (pintype "passive"))
    )
    (net (code "15") (name "/19") (class "Default")
      (node (ref "DDR1") (pin "130") (pinfunction "130_130") (pintype "passive"))
      (node (ref "U1") (pin "19") (pinfunction "LCD_D10__/LCD_G7/_GPIO68_/UART9_RX/__UART8_CTS_19") (pintype "passive"))
    )
    (net (code "16") (name "/20") (class "Default")
      (node (ref "DDR1") (pin "128") (pinfunction "128_128") (pintype "passive"))
      (node (ref "U1") (pin "20") (pinfunction "LCD_R3__/LCD_D11_/GPIO69_/UART9_TX/__UART8_RTS_20") (pintype "passive"))
    )
    (net (code "17") (name "/21") (class "Default")
      (node (ref "DDR1") (pin "126") (pinfunction "126_126") (pintype "passive"))
      (node (ref "U1") (pin "21") (pinfunction "LCD_D12__/LCD_R4__/GPIO70_/UART10_RX/__UART8_DSR_21") (pintype "passive"))
    )
    (net (code "18") (name "/23") (class "Default")
      (node (ref "DDR1") (pin "124") (pinfunction "124_124") (pintype "passive"))
      (node (ref "U1") (pin "23") (pinfunction "LCD_D13_/LCD_R5__/GPIO71_/UART10_TX/__UART8_DTR_23") (pintype "passive"))
    )
    (net (code "19") (name "/24") (class "Default")
      (node (ref "DDR1") (pin "122") (pinfunction "122_122") (pintype "passive"))
      (node (ref "U1") (pin "24") (pinfunction "LCD_D14__/LCD_R6__/GPIO72_/UART11_RX/__UART8_DCD_24") (pintype "passive"))
    )
    (net (code "20") (name "/25") (class "Default")
      (node (ref "DDR1") (pin "120") (pinfunction "120_120") (pintype "passive"))
      (node (ref "U1") (pin "25") (pinfunction "LCD_D15__/LCD_R7__/GPIO73_/UART11_TX/__UART8_RI_25") (pintype "passive"))
    )
    (net (code "21") (name "/70") (class "Default")
      (node (ref "DDR1") (pin "102") (pinfunction "102_102") (pintype "passive"))
      (node (ref "U1") (pin "70") (pinfunction "I2S_DI_/GPIO87_/UART7_RX_70") (pintype "passive"))
    )
    (net (code "22") (name "/71") (class "Default")
      (node (ref "DDR1") (pin "100") (pinfunction "100_100") (pintype "passive"))
      (node (ref "U1") (pin "71") (pinfunction "I2S_DO_/GPIO88_/UART7_TX_71") (pintype "passive"))
    )
    (net (code "23") (name "/72") (class "Default")
      (node (ref "DDR1") (pin "98") (pinfunction "98_98") (pintype "passive"))
      (node (ref "U1") (pin "72") (pinfunction "I2S_LRCK_/GPIO89_/UART8_RX_72") (pintype "passive"))
    )
    (net (code "24") (name "/73") (class "Default")
      (node (ref "DDR1") (pin "96") (pinfunction "96_96") (pintype "passive"))
      (node (ref "U1") (pin "73") (pinfunction "I2S_BCLK_/GPIO90_/UART8_TX_73") (pintype "passive"))
    )
    (net (code "25") (name "/74") (class "Default")
      (node (ref "DDR1") (pin "94") (pinfunction "94_94") (pintype "passive"))
      (node (ref "U1") (pin "74") (pinfunction "I2C_SDA0_/GPIO85_/UART9_RX/__UART8_CTS_74") (pintype "passive"))
    )
    (net (code "26") (name "/75") (class "Default")
      (node (ref "DDR1") (pin "92") (pinfunction "92_92") (pintype "passive"))
      (node (ref "U1") (pin "75") (pinfunction "I2C_SCL0__/GPIO86_/UART9_TX/__UART8_RTS_75") (pintype "passive"))
    )
    (net (code "27") (name "/76") (class "Default")
      (node (ref "DDR1") (pin "90") (pinfunction "90_90") (pintype "passive"))
      (node (ref "U1") (pin "76") (pinfunction "I2S_MCLK_/GPIO91_76") (pintype "passive"))
    )
    (net (code "28") (name "/77") (class "Default")
      (node (ref "DDR1") (pin "88") (pinfunction "88_88") (pintype "passive"))
      (node (ref "U1") (pin "77") (pinfunction "PWM1_/GPIO92_/ADC_YN_77") (pintype "passive"))
    )
    (net (code "29") (name "/78") (class "Default")
      (node (ref "DDR1") (pin "86") (pinfunction "86_86") (pintype "passive"))
      (node (ref "U1") (pin "78") (pinfunction "PWM0/__CAMCLKOUT__/GPIO06_/ADC_XN_78") (pintype "passive"))
    )
    (net (code "30") (name "/79") (class "Default")
      (node (ref "DDR1") (pin "84") (pinfunction "84_84") (pintype "passive"))
      (node (ref "U1") (pin "79") (pinfunction "SPI0_CS2_/GPIO83_/Sdio_Dat3_79") (pintype "passive"))
    )
    (net (code "31") (name "/82") (class "Default")
      (node (ref "DDR1") (pin "82") (pinfunction "82_82") (pintype "passive"))
      (node (ref "U1") (pin "82") (pinfunction "ADC_VREF_82") (pintype "passive"))
    )
    (net (code "32") (name "/85") (class "Default")
      (node (ref "DDR1") (pin "80") (pinfunction "80_80") (pintype "passive"))
      (node (ref "U1") (pin "85") (pinfunction "ADC_D0_85") (pintype "passive"))
    )
    (net (code "33") (name "/86") (class "Default")
      (node (ref "DDR1") (pin "78") (pinfunction "78_78") (pintype "passive"))
      (node (ref "U1") (pin "86") (pinfunction "ADC_D1_86") (pintype "passive"))
    )
    (net (code "34") (name "/87") (class "Default")
      (node (ref "DDR1") (pin "76") (pinfunction "76_76") (pintype "passive"))
      (node (ref "U1") (pin "87") (pinfunction "ADC_XP_87") (pintype "passive"))
    )
    (net (code "35") (name "/88") (class "Default")
      (node (ref "DDR1") (pin "74") (pinfunction "74_74") (pintype "passive"))
      (node (ref "U1") (pin "88") (pinfunction "ADC_YP_88") (pintype "passive"))
    )
    (net (code "36") (name "/89") (class "Default")
      (node (ref "DDR1") (pin "111") (pinfunction "111_111") (pintype "passive"))
      (node (ref "U1") (pin "89") (pinfunction "SPI0_CS3_/GPIO84_/CAMCLKOUT_/UART10_RX/__UART8_DSR_89") (pintype "passive"))
    )
    (net (code "37") (name "/93") (class "Default")
      (node (ref "DDR1") (pin "113") (pinfunction "113_113") (pintype "passive"))
      (node (ref "U1") (pin "93") (pinfunction "SPI0_CS1_/GPIO82_/Sdio_Dat2_/UART10_TX/__UART8_DTR_93") (pintype "passive"))
    )
    (net (code "38") (name "/103") (class "Default")
      (node (ref "DDR1") (pin "115") (pinfunction "115_115") (pintype "passive"))
      (node (ref "U1") (pin "103") (pinfunction "CAMDATA7_/GPIO57_/LCD_R2_/CAN1_TX_/I2C_SCL2_/UART7_RX_103") (pintype "passive"))
    )
    (net (code "39") (name "/104") (class "Default")
      (node (ref "DDR1") (pin "117") (pinfunction "117_117") (pintype "passive"))
      (node (ref "U1") (pin "104") (pinfunction "CAMDATA6_/GPIO56_/LCD_R1_/CAN1_RX_/I2C_SDA2_/UART7_TX_104") (pintype "passive"))
    )
    (net (code "40") (name "/105") (class "Default")
      (node (ref "DDR1") (pin "119") (pinfunction "119_119") (pintype "passive"))
      (node (ref "U1") (pin "105") (pinfunction "CAMDATA5_/GPIO55_/LCD_R0_/CAN0_TX_/I2C_SCL1_/UART8_RX_105") (pintype "passive"))
    )
    (net (code "41") (name "/106") (class "Default")
      (node (ref "DDR1") (pin "121") (pinfunction "121_121") (pintype "passive"))
      (node (ref "U1") (pin "106") (pinfunction "CAMDATA4_/GPIO54_/LCD_G1_/CAN0_RX_/I2C_SDA1_/UART8_TX_106") (pintype "passive"))
    )
    (net (code "42") (name "/107") (class "Default")
      (node (ref "DDR1") (pin "123") (pinfunction "123_123") (pintype "passive"))
      (node (ref "U1") (pin "107") (pinfunction "CAMDATA3_/GPIO53_/LCD_G0_/CAMCLKOUT_/PWM3_/UART9_RX/__UART8_CTS_107") (pintype "passive"))
    )
    (net (code "43") (name "/108") (class "Default")
      (node (ref "DDR1") (pin "125") (pinfunction "125_125") (pintype "passive"))
      (node (ref "U1") (pin "108") (pinfunction "CAMDATA2_/GPIO52_/LCD_B2_/SPI1_CS3_/PWM2_/UART9_TX/__UART8_RTS_108") (pintype "passive"))
    )
    (net (code "44") (name "/109") (class "Default")
      (node (ref "DDR1") (pin "127") (pinfunction "127_127") (pintype "passive"))
      (node (ref "U1") (pin "109") (pinfunction "CAMDATA1_/GPIO51_/LCD_B1_/SPI1_CS2_/I2C_SCL2_/UART10_RX/__UART8_DSR_109") (pintype "passive"))
    )
    (net (code "45") (name "/110") (class "Default")
      (node (ref "DDR1") (pin "129") (pinfunction "129_129") (pintype "passive"))
      (node (ref "U1") (pin "110") (pinfunction "CAMDATA0_/GPIO50_/LCD_B0_/SPI1_CS1_/I2C_SDA2_/UART10_TX/__UART8_DTR_110") (pintype "passive"))
    )
    (net (code "46") (name "/112") (class "Default")
      (node (ref "DDR1") (pin "131") (pinfunction "131_131") (pintype "passive"))
      (node (ref "U1") (pin "112") (pinfunction "CAMHSYNC_/GPIO49_/NAND_RDY3_/SPI1_CS0_/I2C_SCL1_/UART11_RX/__UART8_DCD_112") (pintype "passive"))
    )
    (net (code "47") (name "/113") (class "Default")
      (node (ref "DDR1") (pin "133") (pinfunction "133_133") (pintype "passive"))
      (node (ref "U1") (pin "113") (pinfunction "CAMVSYNC_/GPIO48_/NAND_CE#3_/SPI1_MOSI_/I2C_SDA1_/UART11_TX/__UART8_RI_113") (pintype "passive"))
    )
    (net (code "48") (name "/114") (class "Default")
      (node (ref "DDR1") (pin "135") (pinfunction "135_135") (pintype "passive"))
      (node (ref "U1") (pin "114") (pinfunction "CAMCLKOUT_/GPIO47_/SRAM_A25_/NAND_RDY2_/SPI1_MISO_/PWM3_/UART6_RX/__UART0_DCD_114") (pintype "passive"))
    )
    (net (code "49") (name "/115") (class "Default")
      (node (ref "DDR1") (pin "137") (pinfunction "137_137") (pintype "passive"))
      (node (ref "U1") (pin "115") (pinfunction "CAMPCLKIN_/GPIO46_/SRAM_A24_/NAND_CE#2_/SPI1_CLK_/PWM2_/UART6_TX/__UART0_RI_115") (pintype "passive"))
    )
    (net (code "50") (name "/116") (class "Default")
      (node (ref "DDR1") (pin "139") (pinfunction "139_139") (pintype "passive"))
      (node (ref "U1") (pin "116") (pinfunction "NAND_7_/GPIO20_/SPI1_CS1/__Sdio_Dat2__/MAC_MDIO_/CAMDATA0_/I2C_SCL2_116") (pintype "passive"))
    )
    (net (code "51") (name "/117") (class "Default")
      (node (ref "DDR1") (pin "141") (pinfunction "141_141") (pintype "passive"))
      (node (ref "U1") (pin "117") (pinfunction "NAND_6_/GPIO19_/SPI1_CS2/__Sdio_Dat3__/MAC_MDC_/CAMDATA1_/I2C_SDA2_117") (pintype "passive"))
    )
    (net (code "52") (name "/118(5)") (class "Default")
      (node (ref "R13") (pin "1") (pinfunction "1_1") (pintype "passive"))
      (node (ref "U1") (pin "118") (pinfunction "NAND_5_/GPIO18_/UART1_TX_/UART3_TX_/CAMDATA2_/PWM2_118") (pintype "passive"))
    )
    (net (code "53") (name "/119(4)") (class "Default")
      (node (ref "R12") (pin "1") (pinfunction "1_1") (pintype "passive"))
      (node (ref "U1") (pin "119") (pinfunction "NAND_4_/GPIO17_/UART1_RX_/UART3_RX_/CAMDATA3_/PWM3_119") (pintype "passive"))
    )
    (net (code "54") (name "/120") (class "Default")
      (node (ref "DDR1") (pin "143") (pinfunction "143_143") (pintype "passive"))
      (node (ref "U1") (pin "120") (pinfunction "NAND_3_/GPIO16_/SPI1_CS0/__Sdio_Dat1__/CAN1_TX_/CAMDATA4_/I2S_LRCK_120") (pintype "passive"))
    )
    (net (code "55") (name "/121") (class "Default")
      (node (ref "DDR1") (pin "145") (pinfunction "145_145") (pintype "passive"))
      (node (ref "U1") (pin "121") (pinfunction "NAND_2_/GPIO15_/SPI1_MOSI/__Sdio_Dat0/CAN1_RX_/CAMDATA5_/I2S_DO_121") (pintype "passive"))
    )
    (net (code "56") (name "/122") (class "Default")
      (node (ref "DDR1") (pin "147") (pinfunction "147_147") (pintype "passive"))
      (node (ref "U1") (pin "122") (pinfunction "NAND_1_/GPIO14_/SPI1_MISO/__Sdio_Cmd__/CAN0_TX_/CAMDATA6_/I2S_BCLK_122") (pintype "passive"))
    )
    (net (code "57") (name "/123") (class "Default")
      (node (ref "DDR1") (pin "149") (pinfunction "149_149") (pintype "passive"))
      (node (ref "U1") (pin "123") (pinfunction "NAND_0_/GPIO13_/SPI1_CLK/__Sdio_clk__/CAN0_RX_/CAMDATA7_/I2S_MCLK_/GPIO_123") (pintype "passive"))
    )
    (net (code "58") (name "/127") (class "Default")
      (node (ref "DDR1") (pin "151") (pinfunction "151_151") (pintype "passive"))
      (node (ref "U1") (pin "127") (pinfunction "NAND_RDY_/GPIO07_127") (pintype "passive"))
    )
    (net (code "59") (name "/128") (class "Default")
      (node (ref "DDR1") (pin "153") (pinfunction "153_153") (pintype "passive"))
      (node (ref "U1") (pin "128") (pinfunction "NAND_CLE_/GPIO08_/GPIO_128") (pintype "passive"))
    )
    (net (code "60") (name "/129") (class "Default")
      (node (ref "DDR1") (pin "155") (pinfunction "155_155") (pintype "passive"))
      (node (ref "U1") (pin "129") (pinfunction "NAND_ALE_/GPIO09_/GPIO_129") (pintype "passive"))
    )
    (net (code "61") (name "/130") (class "Default")
      (node (ref "DDR1") (pin "157") (pinfunction "157_157") (pintype "passive"))
      (node (ref "U1") (pin "130") (pinfunction "NAND_RD#_/GPIO10_/GPIO_130") (pintype "passive"))
    )
    (net (code "62") (name "/132") (class "Default")
      (node (ref "DDR1") (pin "159") (pinfunction "159_159") (pintype "passive"))
      (node (ref "U1") (pin "132") (pinfunction "NAND_CE#_/GPIO11_/GPIO_132") (pintype "passive"))
    )
    (net (code "63") (name "/133") (class "Default")
      (node (ref "DDR1") (pin "204") (pinfunction "204_204") (pintype "passive"))
      (node (ref "U1") (pin "133") (pinfunction "NAND_WR#_/GPIO12_/GPIO_133") (pintype "passive"))
    )
    (net (code "64") (name "/134") (class "Default")
      (node (ref "DDR1") (pin "202") (pinfunction "202_202") (pintype "passive"))
      (node (ref "U1") (pin "134") (pinfunction "MAC_TXEN_/GPIO21_/I2S_MCLK_/NAND_CLE_/I2C_SDA2_/CAN0_RX_/UART8_RX_134") (pintype "passive"))
    )
    (net (code "65") (name "/135") (class "Default")
      (node (ref "DDR1") (pin "200") (pinfunction "200_200") (pintype "passive"))
      (node (ref "U1") (pin "135") (pinfunction "MAC_TXD0_/GPIO23_/I2S_DO_/NAND_ALE_/UART0_RX_/CAN1_RX_/UART4_RX/__UART0_CTS_135") (pintype "passive"))
    )
    (net (code "66") (name "/136") (class "Default")
      (node (ref "DDR1") (pin "198") (pinfunction "198_198") (pintype "passive"))
      (node (ref "U1") (pin "136") (pinfunction "MAC_TXD1_/GPIO24_/I2S_LRCK_/NAND_WR#_/UART0_TX_/CAN1_TX_/UART4_TX/__UART0_RTS_136") (pintype "passive"))
    )
    (net (code "67") (name "/137") (class "Default")
      (node (ref "DDR1") (pin "196") (pinfunction "196_196") (pintype "passive"))
      (node (ref "U1") (pin "137") (pinfunction "MAC_RXER_/GPIO25_/I2S_DI_/NAND_RDY0_/I2C_SDA1_/CAMCLKOUT_/UART5_RX/__UART0_DSR_137") (pintype "passive"))
    )
    (net (code "68") (name "/138") (class "Default")
      (node (ref "DDR1") (pin "194") (pinfunction "194_194") (pintype "passive"))
      (node (ref "U1") (pin "138") (pinfunction "MAC_RXDV_/GPIO26_/SPI1_CS3_/NAND_CE#0_/I2C_SCL1_/CAMPCLKIN_/UART5_TX/__UART0_DTR__/GPIO_138") (pintype "passive"))
    )
    (net (code "69") (name "/139") (class "Default")
      (node (ref "DDR1") (pin "192") (pinfunction "192_192") (pintype "passive"))
      (node (ref "U1") (pin "139") (pinfunction "MAC_RXD0_/GPIO27_/I2C_SDA_/PWM2_/UART2_RX_/CAMVSYNC_/UART6_RX/__UART0_DCD__/GPIO_139") (pintype "passive"))
    )
    (net (code "70") (name "/140") (class "Default")
      (node (ref "DDR1") (pin "190") (pinfunction "190_190") (pintype "passive"))
      (node (ref "U1") (pin "140") (pinfunction "MAC_RXD1_/GPIO28_/I2C_SCL_/PWM3_/UART2_TX_/CAMHSYNC_/UART6_TX/__UART0_RI__/GPIO_140") (pintype "passive"))
    )
    (net (code "71") (name "/141") (class "Default")
      (node (ref "DDR1") (pin "188") (pinfunction "188_188") (pintype "passive"))
      (node (ref "U1") (pin "141") (pinfunction "MAC_MDC_/GPIO29_/CAMDATA7_/NAND_CE#1_/PWM2_/I2C_SCL1_/UART8_TX_/GPIO_141") (pintype "passive"))
    )
    (net (code "72") (name "/143") (class "Default")
      (node (ref "DDR1") (pin "186") (pinfunction "186_186") (pintype "passive"))
      (node (ref "U1") (pin "143") (pinfunction "MAC_MDIO_/GPIO30_/CAMDATA6_/NAND_RDY1_/LCD_B0_/I2C_SDA1_/GPIO_143") (pintype "passive"))
    )
    (net (code "73") (name "/144") (class "Default")
      (node (ref "DDR1") (pin "184") (pinfunction "184_184") (pintype "passive"))
      (node (ref "U1") (pin "144") (pinfunction "MAC_RXD2_/GPIO31_/CAMDATA5_/NAND_CS#2_/LCD_B1_/CAN1_RX_/UART11_RX/__UART8_DCD__/GPIO_144") (pintype "passive"))
    )
    (net (code "74") (name "/145") (class "Default")
      (node (ref "D1") (pin "K") (pinfunction "K_K") (pintype "passive"))
      (node (ref "U1") (pin "145") (pinfunction "MAC_TXD2_/GPIO32_/CAMDATA4_/NAND_RDY2_/LCD_B2_/CAN1_TX_/UART11_TX/__UART8_RI_145") (pintype "passive"))
    )
    (net (code "75") (name "/146") (class "Default")
      (node (ref "DDR1") (pin "182") (pinfunction "182_182") (pintype "passive"))
      (node (ref "U1") (pin "146") (pinfunction "MAC_RXD3_/GPIO33_/CAMDATA3_/UART3_RX_/LCD_G0_/SPI1_CLK/__Sdio_clk_146") (pintype "passive"))
    )
    (net (code "76") (name "/147") (class "Default")
      (node (ref "DDR1") (pin "180") (pinfunction "180_180") (pintype "passive"))
      (node (ref "U1") (pin "147") (pinfunction "MAC_TXD3_/GPIO34_/CAMDATA2_/UART3_TX_/LCD_G1_/SPI1_MISO/__Sdio_Cmd_147") (pintype "passive"))
    )
    (net (code "77") (name "/148") (class "Default")
      (node (ref "DDR1") (pin "178") (pinfunction "178_178") (pintype "passive"))
      (node (ref "U1") (pin "148") (pinfunction "MAC_TXC_/GPIO22_/I2S_BCLK_/NAND_RD#_/I2C_SCL2_/CANO_TX_/SDRAM_CS1_148") (pintype "passive"))
    )
    (net (code "78") (name "/151") (class "Default")
      (node (ref "DDR1") (pin "176") (pinfunction "176_176") (pintype "passive"))
      (node (ref "U1") (pin "151") (pinfunction "MAC_CRS__(ONLY_MII)_/GPIO35_/CAMDATA1_/PWM1_/LCD_R0_/SPI1_MOSI/__Sdio_Dat0_151") (pintype "passive"))
    )
    (net (code "79") (name "/157") (class "Default")
      (node (ref "DDR1") (pin "174") (pinfunction "174_174") (pintype "passive"))
      (node (ref "U1") (pin "157") (pinfunction "OTG_DM_157") (pintype "passive"))
    )
    (net (code "80") (name "/158") (class "Default")
      (node (ref "DDR1") (pin "172") (pinfunction "172_172") (pintype "passive"))
      (node (ref "U1") (pin "158") (pinfunction "OTG_DP_158") (pintype "passive"))
    )
    (net (code "81") (name "/160") (class "Default")
      (node (ref "DDR1") (pin "170") (pinfunction "170_170") (pintype "passive"))
      (node (ref "U1") (pin "160") (pinfunction "OTG_VBUS_160") (pintype "passive"))
    )
    (net (code "82") (name "/161") (class "Default")
      (node (ref "DDR1") (pin "168") (pinfunction "168_168") (pintype "passive"))
      (node (ref "U1") (pin "161") (pinfunction "OTG_ID_161") (pintype "passive"))
    )
    (net (code "83") (name "/168") (class "Default")
      (node (ref "DDR1") (pin "166") (pinfunction "166_166") (pintype "passive"))
      (node (ref "U1") (pin "168") (pinfunction "USB_DM_168") (pintype "passive"))
    )
    (net (code "84") (name "/169") (class "Default")
      (node (ref "DDR1") (pin "164") (pinfunction "164_164") (pintype "passive"))
      (node (ref "U1") (pin "169") (pinfunction "USB_DP_169") (pintype "passive"))
    )
    (net (code "85") (name "/CH_CLK_SPI0_CLK") (class "Default")
      (node (ref "U5") (pin "18") (pinfunction "D3_18") (pintype "bidirectional"))
      (node (ref "U6") (pin "2") (pinfunction "S1A_2") (pintype "passive"))
    )
    (net (code "86") (name "/CH_MISO_SPI0_MISO") (class "Default")
      (node (ref "U5") (pin "22") (pinfunction "D7_22") (pintype "bidirectional"))
      (node (ref "U6") (pin "11") (pinfunction "S1C_11") (pintype "passive"))
    )
    (net (code "87") (name "/CH_MOSI_SPI0_MOSI") (class "Default")
      (node (ref "U5") (pin "20") (pinfunction "D5_20") (pintype "bidirectional"))
      (node (ref "U6") (pin "5") (pinfunction "S1B_5") (pintype "passive"))
    )
    (net (code "88") (name "/CH_SDA") (class "Default")
      (node (ref "R32") (pin "1") (pinfunction "1_1") (pintype "passive"))
      (node (ref "S1") (pin "2") (pinfunction "2_2") (pintype "passive"))
      (node (ref "U5") (pin "23") (pinfunction "SDA_23") (pintype "bidirectional"))
      (node (ref "U6") (pin "1") (pinfunction "IN_1") (pintype "passive"))
    )
    (net (code "89") (name "/D+") (class "Default")
      (node (ref "J1") (pin "A6") (pinfunction "D+_A6") (pintype "passive"))
      (node (ref "U5") (pin "10") (pinfunction "UD+_10") (pintype "bidirectional"))
    )
    (net (code "90") (name "/D-") (class "Default")
      (node (ref "J1") (pin "A7") (pinfunction "D-_A7") (pintype "passive"))
      (node (ref "U5") (pin "11") (pinfunction "UD-_11") (pintype "bidirectional"))
    )
    (net (code "91") (name "/EJTAG_RST") (class "Default")
      (node (ref "JP1") (pin "1") (pinfunction "1_1") (pintype "passive"))
      (node (ref "R23") (pin "1") (pinfunction "1_1") (pintype "passive"))
      (node (ref "U1") (pin "100") (pinfunction "EJTAG_RST_/GPIO05_/CAMDATA0_/I2C_SCL2_/PWM1_/UART2_TX_/GPIO_100") (pintype "passive"))
    )
    (net (code "92") (name "/EJTAG_SEL") (class "Default")
      (node (ref "R25") (pin "1") (pinfunction "1_1") (pintype "passive"))
      (node (ref "R26") (pin "1") (pinfunction "1_1") (pintype "passive"))
      (node (ref "U1") (pin "95") (pinfunction "EJTAG_SEL_/GPIO00_/CAMCLKOUT_/I2C_SDA0_/CAN0_RX_/UART3_RX_/SDRAM_CS1_/GPIO_95") (pintype "passive"))
    )
    (net (code "93") (name "/EJTAG_TCK") (class "Default")
      (node (ref "JP1") (pin "5") (pinfunction "5_5") (pintype "passive"))
      (node (ref "R6") (pin "2") (pinfunction "2_2") (pintype "passive"))
      (node (ref "U1") (pin "96") (pinfunction "EJTAG_TCK_/GPIO01_/CAMPCLKIN_/I2C_SCL0_/CAN0_TX_/UART3_TX_/GPIO_96") (pintype "passive"))
    )
    (net (code "94") (name "/EJTAG_TDI") (class "Default")
      (node (ref "JP1") (pin "2") (pinfunction "2_2") (pintype "passive"))
      (node (ref "R10") (pin "1") (pinfunction "1_1") (pintype "passive"))
      (node (ref "R9") (pin "1") (pinfunction "1_1") (pintype "passive"))
      (node (ref "U1") (pin "99") (pinfunction "EJTAG_TDI_/GPIO02_/CAMVSYNC_/I2C_SDA1_/CAN1_RX_/UART1_RX_/GPIO_99") (pintype "passive"))
    )
    (net (code "95") (name "/EJTAG_TDO") (class "Default")
      (node (ref "JP1") (pin "3") (pinfunction "3_3") (pintype "passive"))
      (node (ref "R6") (pin "4") (pinfunction "4_4") (pintype "passive"))
      (node (ref "U1") (pin "98") (pinfunction "EJTAG_TDO_/GPIO03_/CAMHSYNC_/I2C_SCL1_/CAN1_TX_/UART1_TX_/GPIO_98") (pintype "passive"))
    )
    (net (code "96") (name "/EJTAG_TMS") (class "Default")
      (node (ref "JP1") (pin "4") (pinfunction "4_4") (pintype "passive"))
      (node (ref "R6") (pin "3") (pinfunction "3_3") (pintype "passive"))
      (node (ref "U1") (pin "97") (pinfunction "EJTAG_TMS_/GPIO04_/CAMDATA1_/I2C_SDA2_/PWM0_/UART2_RX_/GPIO_97") (pintype "passive"))
    )
    (net (code "97") (name "/FLASH_CS0") (class "Default")
      (node (ref "R27") (pin "2") (pinfunction "2_2") (pintype "passive"))
      (node (ref "U3") (pin "1") (pinfunction "~{CS}_1") (pintype "passive"))
      (node (ref "U6") (pin "12") (pinfunction "DD_12") (pintype "passive"))
    )
    (net (code "98") (name "/JTAG_SEL") (class "Default")
      (node (ref "JP1") (pin "6") (pinfunction "6_6") (pintype "passive"))
      (node (ref "R22") (pin "1") (pinfunction "1_1") (pintype "passive"))
      (node (ref "R24") (pin "1") (pinfunction "1_1") (pintype "passive"))
      (node (ref "U1") (pin "126") (pinfunction "JTAG_SEL_/SDRAM_CS1_/UART6_TX/__UART0_RI_126") (pintype "passive"))
    )
    (net (code "99") (name "/RTCI") (class "Default")
      (node (ref "C3") (pin "2") (pinfunction "2_2") (pintype "passive"))
      (node (ref "R1") (pin "1") (pinfunction "1_1") (pintype "passive"))
      (node (ref "U1") (pin "175") (pinfunction "RTC_CLK_I_175") (pintype "passive"))
      (node (ref "X2") (pin "1") (pinfunction "1_1") (pintype "passive"))
    )
    (net (code "100") (name "/RTCO") (class "Default")
      (node (ref "C4") (pin "2") (pinfunction "2_2") (pintype "passive"))
      (node (ref "R1") (pin "2") (pinfunction "2_2") (pintype "passive"))
      (node (ref "U1") (pin "174") (pinfunction "RTC_CLK_O_174") (pintype "passive"))
      (node (ref "X2") (pin "2") (pinfunction "2_2") (pintype "passive"))
    )
    (net (code "101") (name "/RTC_VDDA") (class "Default")
      (node (ref "DDR1") (pin "163") (pinfunction "163_163") (pintype "passive"))
      (node (ref "U1") (pin "176") (pinfunction "RTC_VR_VDDA_176") (pintype "passive"))
      (node (ref "VD1") (pin "2") (pinfunction "K_2") (pintype "passive"))
    )
    (net (code "102") (name "/SDRAM_A0") (class "Default")
      (node (ref "U1") (pin "67") (pinfunction "SD_A00/__SRAM_A00_67") (pintype "passive"))
      (node (ref "U2") (pin "23") (pinfunction "A0_23") (pintype "passive"))
    )
    (net (code "103") (name "/SDRAM_A1") (class "Default")
      (node (ref "U1") (pin "66") (pinfunction "SD_A01/__SRAM_A01_66") (pintype "passive"))
      (node (ref "U2") (pin "24") (pinfunction "A1_24") (pintype "passive"))
    )
    (net (code "104") (name "/SDRAM_A2") (class "Default")
      (node (ref "U1") (pin "65") (pinfunction "SD_A02/__SRAM_A02_65") (pintype "passive"))
      (node (ref "U2") (pin "25") (pinfunction "A2_25") (pintype "passive"))
    )
    (net (code "105") (name "/SDRAM_A3") (class "Default")
      (node (ref "U1") (pin "64") (pinfunction "SD_A03/__SRAM_A03_64") (pintype "passive"))
      (node (ref "U2") (pin "26") (pinfunction "A3_26") (pintype "passive"))
    )
    (net (code "106") (name "/SDRAM_A4") (class "Default")
      (node (ref "U1") (pin "63") (pinfunction "SD_A04/__SRAM_A04_63") (pintype "passive"))
      (node (ref "U2") (pin "29") (pinfunction "A4_29") (pintype "passive"))
    )
    (net (code "107") (name "/SDRAM_A5") (class "Default")
      (node (ref "U1") (pin "62") (pinfunction "SD_A05/__SRAM_A05_62") (pintype "passive"))
      (node (ref "U2") (pin "30") (pinfunction "A5_30") (pintype "passive"))
    )
    (net (code "108") (name "/SDRAM_A6") (class "Default")
      (node (ref "U1") (pin "61") (pinfunction "SD_A06/__SRAM_A06_61") (pintype "passive"))
      (node (ref "U2") (pin "31") (pinfunction "A6_31") (pintype "passive"))
    )
    (net (code "109") (name "/SDRAM_A7") (class "Default")
      (node (ref "U1") (pin "60") (pinfunction "SD_A07/__SRAM_A07_60") (pintype "passive"))
      (node (ref "U2") (pin "32") (pinfunction "A7_32") (pintype "passive"))
    )
    (net (code "110") (name "/SDRAM_A8") (class "Default")
      (node (ref "U1") (pin "59") (pinfunction "SD_A08/__SRAM_A08_59") (pintype "passive"))
      (node (ref "U2") (pin "33") (pinfunction "A8_33") (pintype "passive"))
    )
    (net (code "111") (name "/SDRAM_A9") (class "Default")
      (node (ref "U1") (pin "58") (pinfunction "SD_A09/__SRAM_A09_58") (pintype "passive"))
      (node (ref "U2") (pin "34") (pinfunction "A9_34") (pintype "passive"))
    )
    (net (code "112") (name "/SDRAM_A10") (class "Default")
      (node (ref "U1") (pin "57") (pinfunction "SD_A10/__SRAM_A10_57") (pintype "passive"))
      (node (ref "U2") (pin "22") (pinfunction "A10_22") (pintype "passive"))
    )
    (net (code "113") (name "/SDRAM_A11") (class "Default")
      (node (ref "U1") (pin "56") (pinfunction "SD_A11/__SRAM_A11_56") (pintype "passive"))
      (node (ref "U2") (pin "35") (pinfunction "A11_35") (pintype "passive"))
    )
    (net (code "114") (name "/SDRAM_A12") (class "Default")
      (node (ref "U1") (pin "55") (pinfunction "SD_A12/__SRAM_A12_55") (pintype "passive"))
      (node (ref "U2") (pin "36") (pinfunction "NC_36") (pintype "passive"))
    )
    (net (code "115") (name "/SDRAM_BA0") (class "Default")
      (node (ref "U1") (pin "52") (pinfunction "SD_BA0/__SRAM_A17_52") (pintype "passive"))
      (node (ref "U2") (pin "20") (pinfunction "BA0_20") (pintype "passive"))
    )
    (net (code "116") (name "/SDRAM_BA1") (class "Default")
      (node (ref "U1") (pin "50") (pinfunction "SD_BA1/__SRAM_A16_50") (pintype "passive"))
      (node (ref "U2") (pin "21") (pinfunction "BA1_21") (pintype "passive"))
    )
    (net (code "117") (name "/SDRAM_CKE") (class "Default")
      (node (ref "U1") (pin "53") (pinfunction "SD_CKE/__SRAM_A13_53") (pintype "passive"))
      (node (ref "U2") (pin "37") (pinfunction "CKE_37") (pintype "passive"))
    )
    (net (code "118") (name "/SDRAM_CLK") (class "Default")
      (node (ref "U1") (pin "54") (pinfunction "SD_CLK/__SRAM_OEn_54") (pintype "passive"))
      (node (ref "U2") (pin "38") (pinfunction "CLK_38") (pintype "passive"))
    )
    (net (code "119") (name "/SDRAM_D0") (class "Default")
      (node (ref "U1") (pin "44") (pinfunction "SD_D00/__SRAM_D00_44") (pintype "passive"))
      (node (ref "U2") (pin "2") (pinfunction "I/O0_2") (pintype "passive"))
    )
    (net (code "120") (name "/SDRAM_D1") (class "Default")
      (node (ref "U1") (pin "43") (pinfunction "SD_D01/__SRAM_D01_43") (pintype "passive"))
      (node (ref "U2") (pin "4") (pinfunction "I/O1_4") (pintype "passive"))
    )
    (net (code "121") (name "/SDRAM_D2") (class "Default")
      (node (ref "U1") (pin "42") (pinfunction "SD_D02/__SRAM_D02_42") (pintype "passive"))
      (node (ref "U2") (pin "5") (pinfunction "I/O2_5") (pintype "passive"))
    )
    (net (code "122") (name "/SDRAM_D3") (class "Default")
      (node (ref "U1") (pin "41") (pinfunction "SD_D03/__SRAM_D03_41") (pintype "passive"))
      (node (ref "U2") (pin "7") (pinfunction "I/O3_7") (pintype "passive"))
    )
    (net (code "123") (name "/SDRAM_D4") (class "Default")
      (node (ref "U1") (pin "40") (pinfunction "SD_D04/__SRAM_D04_40") (pintype "passive"))
      (node (ref "U2") (pin "8") (pinfunction "I/O4_8") (pintype "passive"))
    )
    (net (code "124") (name "/SDRAM_D5") (class "Default")
      (node (ref "U1") (pin "39") (pinfunction "SD_D05/__SRAM_D05_39") (pintype "passive"))
      (node (ref "U2") (pin "10") (pinfunction "I/O5_10") (pintype "passive"))
    )
    (net (code "125") (name "/SDRAM_D6") (class "Default")
      (node (ref "U1") (pin "38") (pinfunction "SD_D06/__SRAM_D06_38") (pintype "passive"))
      (node (ref "U2") (pin "11") (pinfunction "I/O6_11") (pintype "passive"))
    )
    (net (code "126") (name "/SDRAM_D7") (class "Default")
      (node (ref "U1") (pin "37") (pinfunction "SD_D07/__SRAM_D07_37") (pintype "passive"))
      (node (ref "U2") (pin "13") (pinfunction "I/O7_13") (pintype "passive"))
    )
    (net (code "127") (name "/SDRAM_D8") (class "Default")
      (node (ref "U1") (pin "34") (pinfunction "SD_D08/__SRAM_D08_/GPIO97_/I2S_MCLK_/NAND_CLE_/I2C_SDA2_/CAN0_RX_34") (pintype "passive"))
      (node (ref "U2") (pin "42") (pinfunction "I/O8_42") (pintype "passive"))
    )
    (net (code "128") (name "/SDRAM_D9") (class "Default")
      (node (ref "U1") (pin "33") (pinfunction "SD_D09/__SRAM_D09_/GPIO98_/I2S_BCLK_/NAND_RD#_/I2C_SCL2_/CANO_TX_33") (pintype "passive"))
      (node (ref "U2") (pin "44") (pinfunction "I/O9_44") (pintype "passive"))
    )
    (net (code "129") (name "/SDRAM_D10") (class "Default")
      (node (ref "U1") (pin "32") (pinfunction "SD_D10/__SRAM_D10__/GPIO99_/I2S_DI_/NAND_ALE_/UART0_RX_/CAN1_RX_32") (pintype "passive"))
      (node (ref "U2") (pin "45") (pinfunction "I/O10_45") (pintype "passive"))
    )
    (net (code "130") (name "/SDRAM_D11") (class "Default")
      (node (ref "U1") (pin "31") (pinfunction "SD_D11/__SRAM_D11__/GPIO100_/I2S_LRCK_/NAND_WR#_/UART0_TX_/CAN1_TX_31") (pintype "passive"))
      (node (ref "U2") (pin "47") (pinfunction "I/O11_47") (pintype "passive"))
    )
    (net (code "131") (name "/SDRAM_D12") (class "Default")
      (node (ref "U1") (pin "30") (pinfunction "SD_D12/__SRAM_D13/_GPIO101_/UART1_RX_/NAND_RDY_/I2C_SDA1_/PWM0_30") (pintype "passive"))
      (node (ref "U2") (pin "48") (pinfunction "I/O12_48") (pintype "passive"))
    )
    (net (code "132") (name "/SDRAM_D13") (class "Default")
      (node (ref "U1") (pin "29") (pinfunction "SD_D13/__SRAM_D13__/GPIO102_/UART1_TX_/NAND_CE#_/I2C_SCL1_/PWM1_29") (pintype "passive"))
      (node (ref "U2") (pin "50") (pinfunction "I/O13_50") (pintype "passive"))
    )
    (net (code "133") (name "/SDRAM_D14") (class "Default")
      (node (ref "U1") (pin "28") (pinfunction "SD_D14/__SRAM_D14__/GPIO103_/I2C_SDA/_PWM2_/UART2_RX_/MDC_28") (pintype "passive"))
      (node (ref "U2") (pin "51") (pinfunction "I/O14_51") (pintype "passive"))
    )
    (net (code "134") (name "/SDRAM_D15") (class "Default")
      (node (ref "U1") (pin "27") (pinfunction "SD_D15/__SRAM_D15_/GPIO104_/I2C_SCL_/PWM3_/UART2_TX_/MDIO_27") (pintype "passive"))
      (node (ref "U2") (pin "53") (pinfunction "I/O15_53") (pintype "passive"))
    )
    (net (code "135") (name "/SDRAM_DQM0") (class "Default")
      (node (ref "U1") (pin "36") (pinfunction "SD_DQM0/__SRAM_BLEn_36") (pintype "passive"))
      (node (ref "U2") (pin "15") (pinfunction "LDQM_15") (pintype "passive"))
    )
    (net (code "136") (name "/SDRAM_DQM1") (class "Default")
      (node (ref "U1") (pin "35") (pinfunction "SD_DQM1/__SRAM_BHEn__/GPIO96_/I2S_DO_/PWM1_/XTALI_/UART6_RX/__UART0_DCD_35") (pintype "passive"))
      (node (ref "U2") (pin "39") (pinfunction "UDQM_39") (pintype "passive"))
    )
    (net (code "137") (name "/SPI0_CLK") (class "Default")
      (node (ref "R7") (pin "3") (pinfunction "3_3") (pintype "passive"))
      (node (ref "U1") (pin "94") (pinfunction "SPI_CLK_/GPIO78_/Sdio_clk_/UART5_TX/__UART0_DTR_94") (pintype "passive"))
      (node (ref "U6") (pin "3") (pinfunction "S2A_3") (pintype "passive"))
    )
    (net (code "138") (name "/SPI0_CS0") (class "Default")
      (node (ref "U1") (pin "92") (pinfunction "SPI0_CS0_/GPIO81_/Sdio_Dat1_/SDRAM_CS1_/UART5_RX/__UART0_DSR_92") (pintype "passive"))
      (node (ref "U6") (pin "13") (pinfunction "S2D_13") (pintype "passive"))
    )
    (net (code "139") (name "/SPI0_MISO") (class "Default")
      (node (ref "R7") (pin "1") (pinfunction "1_1") (pintype "passive"))
      (node (ref "U1") (pin "90") (pinfunction "SPI0_MISO_/GPIO80_/Sdio_Cmd_/UART4_RX/__UART0_CTS_90") (pintype "passive"))
      (node (ref "U6") (pin "10") (pinfunction "S2C_10") (pintype "passive"))
    )
    (net (code "140") (name "/SPI0_MOSI") (class "Default")
      (node (ref "R7") (pin "2") (pinfunction "2_2") (pintype "passive"))
      (node (ref "U1") (pin "91") (pinfunction "SPI0_MOSI_/GPIO79_/Sdio_Dat0_/UART4_TX/__UART0_RTS_91") (pintype "passive"))
      (node (ref "U6") (pin "6") (pinfunction "S2B_6") (pintype "passive"))
    )
    (net (code "141") (name "/UART2_RX") (class "Default")
      (node (ref "U1") (pin "149") (pinfunction "MAC_COL_/GPIO36_/CAMDATA0_/UART2_RX_/LCD_R1_/SPI1_CS0/__Sdio_Dat1_149") (pintype "passive"))
      (node (ref "U5") (pin "5") (pinfunction "ERR#_5") (pintype "passive"))
    )
    (net (code "142") (name "/UART2_TX") (class "Default")
      (node (ref "U1") (pin "150") (pinfunction "MAC_RXC_/GPIO37_/PWM3_/UART2_TX_/LCD_R2_/SPI1_CS1/__Sdio_Dat2_150") (pintype "passive"))
      (node (ref "U5") (pin "6") (pinfunction "PEMP_6") (pintype "passive"))
    )
    (net (code "143") (name "/W_CLK") (class "Default")
      (node (ref "U3") (pin "6") (pinfunction "CLK_6") (pintype "passive"))
      (node (ref "U6") (pin "4") (pinfunction "DA_4") (pintype "passive"))
    )
    (net (code "144") (name "/W_MISO") (class "Default")
      (node (ref "U3") (pin "2") (pinfunction "MISO_2") (pintype "passive"))
      (node (ref "U6") (pin "9") (pinfunction "DC_9") (pintype "passive"))
    )
    (net (code "145") (name "/W_MOSI") (class "Default")
      (node (ref "U3") (pin "5") (pinfunction "MOSI_5") (pintype "passive"))
      (node (ref "U6") (pin "7") (pinfunction "DB_7") (pintype "passive"))
    )
    (net (code "146") (name "/XTALI") (class "Default")
      (node (ref "C1") (pin "2") (pinfunction "2_2") (pintype "passive"))
      (node (ref "R2") (pin "1") (pinfunction "1_1") (pintype "passive"))
      (node (ref "U1") (pin "1") (pinfunction "XTALI_1") (pintype "passive"))
      (node (ref "X1") (pin "1") (pinfunction "1_1") (pintype "passive"))
    )
    (net (code "147") (name "/XTALO") (class "Default")
      (node (ref "C2") (pin "2") (pinfunction "2_2") (pintype "passive"))
      (node (ref "R2") (pin "2") (pinfunction "2_2") (pintype "passive"))
      (node (ref "U1") (pin "2") (pinfunction "XTAL0_2") (pintype "passive"))
      (node (ref "X1") (pin "3") (pinfunction "3_3") (pintype "passive"))
    )
    (net (code "148") (name "/~{CH_CS}") (class "Default")
      (node (ref "U5") (pin "15") (pinfunction "D0_15") (pintype "bidirectional"))
      (node (ref "U6") (pin "14") (pinfunction "S1D_14") (pintype "passive"))
    )
    (net (code "149") (name "/~{SDRAM_CAS}") (class "Default")
      (node (ref "R8") (pin "3") (pinfunction "3_3") (pintype "passive"))
      (node (ref "U1") (pin "47") (pinfunction "SD_CASn/__SRAM_A15_47") (pintype "passive"))
      (node (ref "U2") (pin "17") (pinfunction "~{CAS}_17") (pintype "passive"))
    )
    (net (code "150") (name "/~{SDRAM_CS}") (class "Default")
      (node (ref "R8") (pin "1") (pinfunction "1_1") (pintype "passive"))
      (node (ref "U1") (pin "49") (pinfunction "SD_CSn/__SRAM_CSn_49") (pintype "passive"))
      (node (ref "U2") (pin "19") (pinfunction "~{CS}_19") (pintype "passive"))
    )
    (net (code "151") (name "/~{SDRAM_RAS}") (class "Default")
      (node (ref "R8") (pin "2") (pinfunction "2_2") (pintype "passive"))
      (node (ref "U1") (pin "48") (pinfunction "SD_RASn/__SRAM_A14_48") (pintype "passive"))
      (node (ref "U2") (pin "18") (pinfunction "~{RAS}_18") (pintype "passive"))
    )
    (net (code "152") (name "/~{SDRAM_WE}") (class "Default")
      (node (ref "R8") (pin "4") (pinfunction "4_4") (pintype "passive"))
      (node (ref "U1") (pin "46") (pinfunction "SD_WEn/__SRAM_WEn_46") (pintype "passive"))
      (node (ref "U2") (pin "16") (pinfunction "~{WE}_16") (pintype "passive"))
    )
    (net (code "153") (name "/~{SPI_HOLD}") (class "Default")
      (node (ref "R28") (pin "1") (pinfunction "1_1") (pintype "passive"))
      (node (ref "U3") (pin "7") (pinfunction "~{HOLD}_7") (pintype "passive"))
    )
    (net (code "154") (name "/~{SPI_WP}") (class "Default")
      (node (ref "R29") (pin "2") (pinfunction "2_2") (pintype "passive"))
      (node (ref "U3") (pin "3") (pinfunction "~{WP}_3") (pintype "passive"))
    )
    (net (code "155") (name "/~{SYS_RESET}") (class "Default")
      (node (ref "C32") (pin "2") (pinfunction "2_2") (pintype "passive"))
      (node (ref "R11") (pin "1") (pinfunction "1_1") (pintype "passive"))
      (node (ref "SW1") (pin "1") (pinfunction "1_1") (pintype "passive"))
      (node (ref "U1") (pin "125") (pinfunction "~{SYS_RST}_125") (pintype "passive"))
    )
    (net (code "156") (name "1V2") (class "Default")
      (node (ref "C20") (pin "2") (pinfunction "2_2") (pintype "passive"))
      (node (ref "C21") (pin "2") (pinfunction "2_2") (pintype "passive"))
      (node (ref "C22") (pin "2") (pinfunction "2_2") (pintype "passive"))
      (node (ref "C23") (pin "2") (pinfunction "2_2") (pintype "passive"))
      (node (ref "C24") (pin "2") (pinfunction "2_2") (pintype "passive"))
      (node (ref "C25") (pin "2") (pinfunction "2_2") (pintype "passive"))
      (node (ref "C26") (pin "2") (pinfunction "2_2") (pintype "passive"))
      (node (ref "C27") (pin "2") (pinfunction "2_2") (pintype "passive"))
      (node (ref "C28") (pin "2") (pinfunction "2_2") (pintype "passive"))
      (node (ref "C29") (pin "2") (pinfunction "2_2") (pintype "passive"))
      (node (ref "C30") (pin "2") (pinfunction "2_2") (pintype "passive"))
      (node (ref "C31") (pin "2") (pinfunction "2_2") (pintype "passive"))
      (node (ref "C56") (pin "1") (pinfunction "1_1") (pintype "passive"))
      (node (ref "L3") (pin "2") (pinfunction "2_2") (pintype "passive"))
      (node (ref "R35") (pin "2") (pinfunction "2_2") (pintype "passive"))
      (node (ref "U1") (pin "101") (pinfunction "CORE_VDD_101") (pintype "passive"))
      (node (ref "U1") (pin "11") (pinfunction "CORE_VDD_11") (pintype "passive"))
      (node (ref "U1") (pin "124") (pinfunction "CORE_VDD_124") (pintype "passive"))
      (node (ref "U1") (pin "152") (pinfunction "CORE_VDD_152") (pintype "passive"))
      (node (ref "U1") (pin "154") (pinfunction "OTG_DVDD_154") (pintype "passive"))
      (node (ref "U1") (pin "164") (pinfunction "USB_DVDD_164") (pintype "passive"))
      (node (ref "U1") (pin "171") (pinfunction "PLL_VDD12_171") (pintype "passive"))
      (node (ref "U1") (pin "26") (pinfunction "CORE_VDD_26") (pintype "passive"))
      (node (ref "U1") (pin "68") (pinfunction "CORE_VDD_68") (pintype "passive"))
    )
    (net (code "157") (name "3V3") (class "Default")
      (node (ref "C10") (pin "2") (pinfunction "2_2") (pintype "passive"))
      (node (ref "C11") (pin "2") (pinfunction "2_2") (pintype "passive"))
      (node (ref "C12") (pin "2") (pinfunction "2_2") (pintype "passive"))
      (node (ref "C13") (pin "2") (pinfunction "2_2") (pintype "passive"))
      (node (ref "C14") (pin "2") (pinfunction "2_2") (pintype "passive"))
      (node (ref "C15") (pin "2") (pinfunction "2_2") (pintype "passive"))
      (node (ref "C16") (pin "2") (pinfunction "2_2") (pintype "passive"))
      (node (ref "C17") (pin "2") (pinfunction "2_2") (pintype "passive"))
      (node (ref "C33") (pin "2") (pinfunction "2_2") (pintype "passive"))
      (node (ref "C34") (pin "2") (pinfunction "2_2") (pintype "passive"))
      (node (ref "C35") (pin "2") (pinfunction "2_2") (pintype "passive"))
      (node (ref "C36") (pin "2") (pinfunction "2_2") (pintype "passive"))
      (node (ref "C37") (pin "2") (pinfunction "2_2") (pintype "passive"))
      (node (ref "C38") (pin "2") (pinfunction "2_2") (pintype "passive"))
      (node (ref "C39") (pin "2") (pinfunction "2_2") (pintype "passive"))
      (node (ref "C40") (pin "2") (pinfunction "2_2") (pintype "passive"))
      (node (ref "C41") (pin "2") (pinfunction "2_2") (pintype "passive"))
      (node (ref "C42") (pin "2") (pinfunction "2_2") (pintype "passive"))
      (node (ref "C43") (pin "2") (pinfunction "2_2") (pintype "passive"))
      (node (ref "C44") (pin "2") (pinfunction "2_2") (pintype "passive"))
      (node (ref "C45") (pin "2") (pinfunction "2_2") (pintype "passive"))
      (node (ref "C46") (pin "2") (pinfunction "2_2") (pintype "passive"))
      (node (ref "C47") (pin "2") (pinfunction "2_2") (pintype "passive"))
      (node (ref "C48") (pin "2") (pinfunction "2_2") (pintype "passive"))
      (node (ref "C49") (pin "2") (pinfunction "2_2") (pintype "passive"))
      (node (ref "C5") (pin "2") (pinfunction "2_2") (pintype "passive"))
      (node (ref "C50") (pin "1") (pinfunction "1_1") (pintype "passive"))
      (node (ref "C52") (pin "2") (pinfunction "2_2") (pintype "passive"))
      (node (ref "C53") (pin "2") (pinfunction "2_2") (pintype "passive"))
      (node (ref "C57") (pin "2") (pinfunction "2_2") (pintype "passive"))
      (node (ref "C6") (pin "2") (pinfunction "2_2") (pintype "passive"))
      (node (ref "C7") (pin "2") (pinfunction "2_2") (pintype "passive"))
      (node (ref "C8") (pin "2") (pinfunction "2_2") (pintype "passive"))
      (node (ref "C9") (pin "2") (pinfunction "2_2") (pintype "passive"))
      (node (ref "L1") (pin "1") (pinfunction "1_1") (pintype "passive"))
      (node (ref "L2") (pin "2") (pinfunction "2_2") (pintype "passive"))
      (node (ref "R11") (pin "2") (pinfunction "2_2") (pintype "passive"))
      (node (ref "R12") (pin "2") (pinfunction "2_2") (pintype "passive"))
      (node (ref "R22") (pin "2") (pinfunction "2_2") (pintype "passive"))
      (node (ref "R25") (pin "2") (pinfunction "2_2") (pintype "passive"))
      (node (ref "R27") (pin "1") (pinfunction "1_1") (pintype "passive"))
      (node (ref "R28") (pin "2") (pinfunction "2_2") (pintype "passive"))
      (node (ref "R29") (pin "1") (pinfunction "1_1") (pintype "passive"))
      (node (ref "R31") (pin "2") (pinfunction "2_2") (pintype "passive"))
      (node (ref "R32") (pin "2") (pinfunction "2_2") (pintype "passive"))
      (node (ref "R34") (pin "1") (pinfunction "1_1") (pintype "passive"))
      (node (ref "R37") (pin "1") (pinfunction "1_1") (pintype "passive"))
      (node (ref "R38") (pin "1") (pinfunction "1_1") (pintype "passive"))
      (node (ref "R5") (pin "2") (pinfunction "2_2") (pintype "passive"))
      (node (ref "R6") (pin "5") (pinfunction "5_5") (pintype "passive"))
      (node (ref "R6") (pin "6") (pinfunction "6_6") (pintype "passive"))
      (node (ref "R6") (pin "7") (pinfunction "7_7") (pintype "passive"))
      (node (ref "R7") (pin "6") (pinfunction "6_6") (pintype "passive"))
      (node (ref "R7") (pin "7") (pinfunction "7_7") (pintype "passive"))
      (node (ref "R7") (pin "8") (pinfunction "8_8") (pintype "passive"))
      (node (ref "R8") (pin "5") (pinfunction "5_5") (pintype "passive"))
      (node (ref "R8") (pin "6") (pinfunction "6_6") (pintype "passive"))
      (node (ref "R8") (pin "7") (pinfunction "7_7") (pintype "passive"))
      (node (ref "R8") (pin "8") (pinfunction "8_8") (pintype "passive"))
      (node (ref "R9") (pin "2") (pinfunction "2_2") (pintype "passive"))
      (node (ref "U1") (pin "102") (pinfunction "IO_VDD_102") (pintype "passive"))
      (node (ref "U1") (pin "131") (pinfunction "IO_VDD_131") (pintype "passive"))
      (node (ref "U1") (pin "155") (pinfunction "OTG_VDD33_155") (pintype "passive"))
      (node (ref "U1") (pin "165") (pinfunction "USB_VDD33_165") (pintype "passive"))
      (node (ref "U1") (pin "173") (pinfunction "PLL_VDD33_173") (pintype "passive"))
      (node (ref "U1") (pin "18") (pinfunction "IO_VDD_18") (pintype "passive"))
      (node (ref "U1") (pin "45") (pinfunction "IO_VDD_45") (pintype "passive"))
      (node (ref "U1") (pin "69") (pinfunction "IO_VDD_69") (pintype "passive"))
      (node (ref "U2") (pin "1") (pinfunction "VCC_1") (pintype "passive"))
      (node (ref "U2") (pin "14") (pinfunction "VCC_14") (pintype "passive"))
      (node (ref "U2") (pin "27") (pinfunction "VCC_27") (pintype "passive"))
      (node (ref "U2") (pin "3") (pinfunction "VCCQ_3") (pintype "passive"))
      (node (ref "U2") (pin "43") (pinfunction "VCCQ_43") (pintype "passive"))
      (node (ref "U2") (pin "49") (pinfunction "VCCQ_49") (pintype "passive"))
      (node (ref "U2") (pin "9") (pinfunction "VCCQ_9") (pintype "passive"))
      (node (ref "U3") (pin "8") (pinfunction "VCC_8") (pintype "passive"))
      (node (ref "U5") (pin "28") (pinfunction "VCC_28") (pintype "power_in"))
      (node (ref "U5") (pin "9") (pinfunction "V3_9") (pintype "power_in"))
      (node (ref "U6") (pin "16") (pinfunction "VCC_16") (pintype "passive"))
      (node (ref "U7") (pin "4") (pinfunction "IN_4") (pintype "passive"))
      (node (ref "VD1") (pin "1") (pinfunction "A_1") (pintype "passive"))
    )
    (net (code "158") (name "5V") (class "Default")
      (node (ref "C51") (pin "2") (pinfunction "2_2") (pintype "passive"))
      (node (ref "F1") (pin "2") (pinfunction "2_2") (pintype "passive"))
      (node (ref "U4") (pin "4") (pinfunction "IN_4") (pintype "passive"))
    )
    (net (code "159") (name "5V1") (class "Default")
      (node (ref "DDR1") (pin "1") (pinfunction "1_1") (pintype "passive"))
      (node (ref "DDR1") (pin "10") (pinfunction "10_10") (pintype "passive"))
      (node (ref "DDR1") (pin "11") (pinfunction "11_11") (pintype "passive"))
      (node (ref "DDR1") (pin "2") (pinfunction "2_2") (pintype "passive"))
      (node (ref "DDR1") (pin "3") (pinfunction "3_3") (pintype "passive"))
      (node (ref "DDR1") (pin "4") (pinfunction "4_4") (pintype "passive"))
      (node (ref "DDR1") (pin "5") (pinfunction "5_5") (pintype "passive"))
      (node (ref "DDR1") (pin "6") (pinfunction "6_6") (pintype "passive"))
      (node (ref "DDR1") (pin "7") (pinfunction "7_7") (pintype "passive"))
      (node (ref "DDR1") (pin "8") (pinfunction "8_8") (pintype "passive"))
      (node (ref "DDR1") (pin "9") (pinfunction "9_9") (pintype "passive"))
      (node (ref "F1") (pin "1") (pinfunction "1_1") (pintype "passive"))
      (node (ref "J1") (pin "A4") (pinfunction "VBUS_A4") (pintype "passive"))
    )
    (net (code "160") (name "ADC_VDDA") (class "Default")
      (node (ref "C18") (pin "2") (pinfunction "2_2") (pintype "passive"))
      (node (ref "C19") (pin "2") (pinfunction "2_2") (pintype "passive"))
      (node (ref "L1") (pin "2") (pinfunction "2_2") (pintype "passive"))
      (node (ref "U1") (pin "83") (pinfunction "ADC_VDDA_83") (pintype "passive"))
    )
    (net (code "161") (name "GND") (class "Default")
      (node (ref "C1") (pin "1") (pinfunction "1_1") (pintype "passive"))
      (node (ref "C10") (pin "1") (pinfunction "1_1") (pintype "passive"))
      (node (ref "C11") (pin "1") (pinfunction "1_1") (pintype "passive"))
      (node (ref "C12") (pin "1") (pinfunction "1_1") (pintype "passive"))
      (node (ref "C13") (pin "1") (pinfunction "1_1") (pintype "passive"))
      (node (ref "C14") (pin "1") (pinfunction "1_1") (pintype "passive"))
      (node (ref "C15") (pin "1") (pinfunction "1_1") (pintype "passive"))
      (node (ref "C16") (pin "1") (pinfunction "1_1") (pintype "passive"))
      (node (ref "C17") (pin "1") (pinfunction "1_1") (pintype "passive"))
      (node (ref "C18") (pin "1") (pinfunction "1_1") (pintype "passive"))
      (node (ref "C19") (pin "1") (pinfunction "1_1") (pintype "passive"))
      (node (ref "C2") (pin "1") (pinfunction "1_1") (pintype "passive"))
      (node (ref "C20") (pin "1") (pinfunction "1_1") (pintype "passive"))
      (node (ref "C21") (pin "1") (pinfunction "1_1") (pintype "passive"))
      (node (ref "C22") (pin "1") (pinfunction "1_1") (pintype "passive"))
      (node (ref "C23") (pin "1") (pinfunction "1_1") (pintype "passive"))
      (node (ref "C24") (pin "1") (pinfunction "1_1") (pintype "passive"))
      (node (ref "C25") (pin "1") (pinfunction "1_1") (pintype "passive"))
      (node (ref "C26") (pin "1") (pinfunction "1_1") (pintype "passive"))
      (node (ref "C27") (pin "1") (pinfunction "1_1") (pintype "passive"))
      (node (ref "C28") (pin "1") (pinfunction "1_1") (pintype "passive"))
      (node (ref "C29") (pin "1") (pinfunction "1_1") (pintype "passive"))
      (node (ref "C3") (pin "1") (pinfunction "1_1") (pintype "passive"))
      (node (ref "C30") (pin "1") (pinfunction "1_1") (pintype "passive"))
      (node (ref "C31") (pin "1") (pinfunction "1_1") (pintype "passive"))
      (node (ref "C32") (pin "1") (pinfunction "1_1") (pintype "passive"))
      (node (ref "C33") (pin "1") (pinfunction "1_1") (pintype "passive"))
      (node (ref "C34") (pin "1") (pinfunction "1_1") (pintype "passive"))
      (node (ref "C35") (pin "1") (pinfunction "1_1") (pintype "passive"))
      (node (ref "C36") (pin "1") (pinfunction "1_1") (pintype "passive"))
      (node (ref "C37") (pin "1") (pinfunction "1_1") (pintype "passive"))
      (node (ref "C38") (pin "1") (pinfunction "1_1") (pintype "passive"))
      (node (ref "C39") (pin "1") (pinfunction "1_1") (pintype "passive"))
      (node (ref "C4") (pin "1") (pinfunction "1_1") (pintype "passive"))
      (node (ref "C40") (pin "1") (pinfunction "1_1") (pintype "passive"))
      (node (ref "C41") (pin "1") (pinfunction "1_1") (pintype "passive"))
      (node (ref "C42") (pin "1") (pinfunction "1_1") (pintype "passive"))
      (node (ref "C43") (pin "1") (pinfunction "1_1") (pintype "passive"))
      (node (ref "C44") (pin "1") (pinfunction "1_1") (pintype "passive"))
      (node (ref "C45") (pin "1") (pinfunction "1_1") (pintype "passive"))
      (node (ref "C46") (pin "1") (pinfunction "1_1") (pintype "passive"))
      (node (ref "C47") (pin "1") (pinfunction "1_1") (pintype "passive"))
      (node (ref "C48") (pin "1") (pinfunction "1_1") (pintype "passive"))
      (node (ref "C5") (pin "1") (pinfunction "1_1") (pintype "passive"))
      (node (ref "C50") (pin "2") (pinfunction "2_2") (pintype "passive"))
      (node (ref "C51") (pin "1") (pinfunction "1_1") (pintype "passive"))
      (node (ref "C52") (pin "1") (pinfunction "1_1") (pintype "passive"))
      (node (ref "C53") (pin "1") (pinfunction "1_1") (pintype "passive"))
      (node (ref "C54") (pin "1") (pinfunction "1_1") (pintype "passive"))
      (node (ref "C55") (pin "1") (pinfunction "1_1") (pintype "passive"))
      (node (ref "C56") (pin "2") (pinfunction "2_2") (pintype "passive"))
      (node (ref "C57") (pin "1") (pinfunction "1_1") (pintype "passive"))
      (node (ref "C6") (pin "1") (pinfunction "1_1") (pintype "passive"))
      (node (ref "C7") (pin "1") (pinfunction "1_1") (pintype "passive"))
      (node (ref "C8") (pin "1") (pinfunction "1_1") (pintype "passive"))
      (node (ref "C9") (pin "1") (pinfunction "1_1") (pintype "passive"))
      (node (ref "D2") (pin "K") (pinfunction "K_K") (pintype "passive"))
      (node (ref "DDR1") (pin "101") (pinfunction "101_101") (pintype "passive"))
      (node (ref "DDR1") (pin "103") (pinfunction "103_103") (pintype "passive"))
      (node (ref "DDR1") (pin "104") (pinfunction "104_104") (pintype "passive"))
      (node (ref "DDR1") (pin "105") (pinfunction "105_105") (pintype "passive"))
      (node (ref "DDR1") (pin "106") (pinfunction "106_106") (pintype "passive"))
      (node (ref "DDR1") (pin "107") (pinfunction "107_107") (pintype "passive"))
      (node (ref "DDR1") (pin "108") (pinfunction "108_108") (pintype "passive"))
      (node (ref "DDR1") (pin "109") (pinfunction "109_109") (pintype "passive"))
      (node (ref "DDR1") (pin "110") (pinfunction "110_110") (pintype "passive"))
      (node (ref "DDR1") (pin "112") (pinfunction "112_112") (pintype "passive"))
      (node (ref "DDR1") (pin "114") (pinfunction "114_114") (pintype "passive"))
      (node (ref "DDR1") (pin "116") (pinfunction "116_116") (pintype "passive"))
      (node (ref "DDR1") (pin "118") (pinfunction "118_118") (pintype "passive"))
      (node (ref "DDR1") (pin "12") (pinfunction "12_12") (pintype "passive"))
      (node (ref "DDR1") (pin "13") (pinfunction "13_13") (pintype "passive"))
      (node (ref "DDR1") (pin "14") (pinfunction "14_14") (pintype "passive"))
      (node (ref "DDR1") (pin "15") (pinfunction "15_15") (pintype "passive"))
      (node (ref "DDR1") (pin "16") (pinfunction "16_16") (pintype "passive"))
      (node (ref "DDR1") (pin "160") (pinfunction "160_160") (pintype "passive"))
      (node (ref "DDR1") (pin "161") (pinfunction "161_161") (pintype "passive"))
      (node (ref "DDR1") (pin "162") (pinfunction "162_162") (pintype "passive"))
      (node (ref "DDR1") (pin "165") (pinfunction "165_165") (pintype "passive"))
      (node (ref "DDR1") (pin "167") (pinfunction "167_167") (pintype "passive"))
      (node (ref "DDR1") (pin "169") (pinfunction "169_169") (pintype "passive"))
      (node (ref "DDR1") (pin "17") (pinfunction "17_17") (pintype "passive"))
      (node (ref "DDR1") (pin "171") (pinfunction "171_171") (pintype "passive"))
      (node (ref "DDR1") (pin "173") (pinfunction "173_173") (pintype "passive"))
      (node (ref "DDR1") (pin "175") (pinfunction "175_175") (pintype "passive"))
      (node (ref "DDR1") (pin "177") (pinfunction "177_177") (pintype "passive"))
      (node (ref "DDR1") (pin "179") (pinfunction "179_179") (pintype "passive"))
      (node (ref "DDR1") (pin "18") (pinfunction "18_18") (pintype "passive"))
      (node (ref "DDR1") (pin "181") (pinfunction "181_181") (pintype "passive"))
      (node (ref "DDR1") (pin "183") (pinfunction "183_183") (pintype "passive"))
      (node (ref "DDR1") (pin "185") (pinfunction "185_185") (pintype "passive"))
      (node (ref "DDR1") (pin "187") (pinfunction "187_187") (pintype "passive"))
      (node (ref "DDR1") (pin "189") (pinfunction "189_189") (pintype "passive"))
      (node (ref "DDR1") (pin "19") (pinfunction "19_19") (pintype "passive"))
      (node (ref "DDR1") (pin "191") (pinfunction "191_191") (pintype "passive"))
      (node (ref "DDR1") (pin "193") (pinfunction "193_193") (pintype "passive"))
      (node (ref "DDR1") (pin "195") (pinfunction "195_195") (pintype "passive"))
      (node (ref "DDR1") (pin "197") (pinfunction "197_197") (pintype "passive"))
      (node (ref "DDR1") (pin "199") (pinfunction "199_199") (pintype "passive"))
      (node (ref "DDR1") (pin "20") (pinfunction "20_20") (pintype "passive"))
      (node (ref "DDR1") (pin "201") (pinfunction "201_201") (pintype "passive"))
      (node (ref "DDR1") (pin "203") (pinfunction "203_203") (pintype "passive"))
      (node (ref "DDR1") (pin "21") (pinfunction "21_21") (pintype "passive"))
      (node (ref "DDR1") (pin "22") (pinfunction "22_22") (pintype "passive"))
      (node (ref "DDR1") (pin "23") (pinfunction "23_23") (pintype "passive"))
      (node (ref "DDR1") (pin "24") (pinfunction "24_24") (pintype "passive"))
      (node (ref "DDR1") (pin "25") (pinfunction "25_25") (pintype "passive"))
      (node (ref "DDR1") (pin "26") (pinfunction "26_26") (pintype "passive"))
      (node (ref "DDR1") (pin "27") (pinfunction "27_27") (pintype "passive"))
      (node (ref "DDR1") (pin "28") (pinfunction "28_28") (pintype "passive"))
      (node (ref "DDR1") (pin "29") (pinfunction "29_29") (pintype "passive"))
      (node (ref "DDR1") (pin "30") (pinfunction "30_30") (pintype "passive"))
      (node (ref "DDR1") (pin "31") (pinfunction "31_31") (pintype "passive"))
      (node (ref "DDR1") (pin "32") (pinfunction "32_32") (pintype "passive"))
      (node (ref "DDR1") (pin "33") (pinfunction "33_33") (pintype "passive"))
      (node (ref "DDR1") (pin "34") (pinfunction "34_34") (pintype "passive"))
      (node (ref "DDR1") (pin "35") (pinfunction "35_35") (pintype "passive"))
      (node (ref "DDR1") (pin "36") (pinfunction "36_36") (pintype "passive"))
      (node (ref "DDR1") (pin "37") (pinfunction "37_37") (pintype "passive"))
      (node (ref "DDR1") (pin "38") (pinfunction "38_38") (pintype "passive"))
      (node (ref "DDR1") (pin "39") (pinfunction "39_39") (pintype "passive"))
      (node (ref "DDR1") (pin "40") (pinfunction "40_40") (pintype "passive"))
      (node (ref "DDR1") (pin "41") (pinfunction "41_41") (pintype "passive"))
      (node (ref "DDR1") (pin "42") (pinfunction "42_42") (pintype "passive"))
      (node (ref "DDR1") (pin "43") (pinfunction "43_43") (pintype "passive"))
      (node (ref "DDR1") (pin "44") (pinfunction "44_44") (pintype "passive"))
      (node (ref "DDR1") (pin "45") (pinfunction "45_45") (pintype "passive"))
      (node (ref "DDR1") (pin "46") (pinfunction "46_46") (pintype "passive"))
      (node (ref "DDR1") (pin "47") (pinfunction "47_47") (pintype "passive"))
      (node (ref "DDR1") (pin "48") (pinfunction "48_48") (pintype "passive"))
      (node (ref "DDR1") (pin "49") (pinfunction "49_49") (pintype "passive"))
      (node (ref "DDR1") (pin "50") (pinfunction "50_50") (pintype "passive"))
      (node (ref "DDR1") (pin "51") (pinfunction "51_51") (pintype "passive"))
      (node (ref "DDR1") (pin "52") (pinfunction "52_52") (pintype "passive"))
      (node (ref "DDR1") (pin "53") (pinfunction "53_53") (pintype "passive"))
      (node (ref "DDR1") (pin "54") (pinfunction "54_54") (pintype "passive"))
      (node (ref "DDR1") (pin "55") (pinfunction "55_55") (pintype "passive"))
      (node (ref "DDR1") (pin "56") (pinfunction "56_56") (pintype "passive"))
      (node (ref "DDR1") (pin "57") (pinfunction "57_57") (pintype "passive"))
      (node (ref "DDR1") (pin "58") (pinfunction "58_58") (pintype "passive"))
      (node (ref "DDR1") (pin "59") (pinfunction "59_59") (pintype "passive"))
      (node (ref "DDR1") (pin "60") (pinfunction "60_60") (pintype "passive"))
      (node (ref "DDR1") (pin "61") (pinfunction "61_61") (pintype "passive"))
      (node (ref "DDR1") (pin "62") (pinfunction "62_62") (pintype "passive"))
      (node (ref "DDR1") (pin "63") (pinfunction "63_63") (pintype "passive"))
      (node (ref "DDR1") (pin "64") (pinfunction "64_64") (pintype "passive"))
      (node (ref "DDR1") (pin "65") (pinfunction "65_65") (pintype "passive"))
      (node (ref "DDR1") (pin "66") (pinfunction "66_66") (pintype "passive"))
      (node (ref "DDR1") (pin "67") (pinfunction "67_67") (pintype "passive"))
      (node (ref "DDR1") (pin "68") (pinfunction "68_68") (pintype "passive"))
      (node (ref "DDR1") (pin "69") (pinfunction "69_69") (pintype "passive"))
      (node (ref "DDR1") (pin "70") (pinfunction "70_70") (pintype "passive"))
      (node (ref "DDR1") (pin "71") (pinfunction "71_71") (pintype "passive"))
      (node (ref "DDR1") (pin "72") (pinfunction "72_72") (pintype "passive"))
      (node (ref "DDR1") (pin "73") (pinfunction "73_73") (pintype "passive"))
      (node (ref "DDR1") (pin "75") (pinfunction "75_75") (pintype "passive"))
      (node (ref "DDR1") (pin "77") (pinfunction "77_77") (pintype "passive"))
      (node (ref "DDR1") (pin "79") (pinfunction "79_79") (pintype "passive"))
      (node (ref "DDR1") (pin "81") (pinfunction "81_81") (pintype "passive"))
      (node (ref "DDR1") (pin "83") (pinfunction "83_83") (pintype "passive"))
      (node (ref "DDR1") (pin "85") (pinfunction "85_85") (pintype "passive"))
      (node (ref "DDR1") (pin "87") (pinfunction "87_87") (pintype "passive"))
      (node (ref "DDR1") (pin "89") (pinfunction "89_89") (pintype "passive"))
      (node (ref "DDR1") (pin "91") (pinfunction "91_91") (pintype "passive"))
      (node (ref "DDR1") (pin "93") (pinfunction "93_93") (pintype "passive"))
      (node (ref "DDR1") (pin "95") (pinfunction "95_95") (pintype "passive"))
      (node (ref "DDR1") (pin "97") (pinfunction "97_97") (pintype "passive"))
      (node (ref "DDR1") (pin "99") (pinfunction "99_99") (pintype "passive"))
      (node (ref "J1") (pin "A1") (pinfunction "GND_A1") (pintype "passive"))
      (node (ref "J1") (pin "S1") (pinfunction "GND_S1") (pintype "passive"))
      (node (ref "JP1") (pin "7") (pinfunction "7_7") (pintype "passive"))
      (node (ref "R10") (pin "2") (pinfunction "2_2") (pintype "passive"))
      (node (ref "R13") (pin "2") (pinfunction "2_2") (pintype "passive"))
      (node (ref "R17") (pin "1") (pinfunction "1_1") (pintype "passive"))
      (node (ref "R23") (pin "2") (pinfunction "2_2") (pintype "passive"))
      (node (ref "R24") (pin "2") (pinfunction "2_2") (pintype "passive"))
      (node (ref "R26") (pin "2") (pinfunction "2_2") (pintype "passive"))
      (node (ref "R3") (pin "1") (pinfunction "1_1") (pintype "passive"))
      (node (ref "R30") (pin "2") (pinfunction "2_2") (pintype "passive"))
      (node (ref "R33") (pin "1") (pinfunction "1_1") (pintype "passive"))
      (node (ref "R36") (pin "1") (pinfunction "1_1") (pintype "passive"))
      (node (ref "R4") (pin "1") (pinfunction "1_1") (pintype "passive"))
      (node (ref "S1") (pin "3") (pinfunction "3_3") (pintype "passive"))
      (node (ref "SW1") (pin "2") (pinfunction "2_2") (pintype "passive"))
      (node (ref "U1") (pin "111") (pinfunction "CORE_VSS_111") (pintype "passive"))
      (node (ref "U1") (pin "142") (pinfunction "CORE_VSS_142") (pintype "passive"))
      (node (ref "U1") (pin "153") (pinfunction "OTG_DVSS_153") (pintype "passive"))
      (node (ref "U1") (pin "156") (pinfunction "OTG_VSS33_156") (pintype "passive"))
      (node (ref "U1") (pin "162") (pinfunction "CORE_VSS_162") (pintype "passive"))
      (node (ref "U1") (pin "163") (pinfunction "USB_DVSS_163") (pintype "passive"))
      (node (ref "U1") (pin "166") (pinfunction "USB_VSS33_166") (pintype "passive"))
      (node (ref "U1") (pin "170") (pinfunction "PLL_VSS12_170") (pintype "passive"))
      (node (ref "U1") (pin "172") (pinfunction "PLL_VSS33_172") (pintype "passive"))
      (node (ref "U1") (pin "22") (pinfunction "CORE_VSS_22") (pintype "passive"))
      (node (ref "U1") (pin "51") (pinfunction "CORE_VSS_51") (pintype "passive"))
      (node (ref "U1") (pin "80") (pinfunction "CORE_VSS_80") (pintype "passive"))
      (node (ref "U1") (pin "84") (pinfunction "ADC_VSSA_84") (pintype "passive"))
      (node (ref "U2") (pin "12") (pinfunction "GNDQ_12") (pintype "passive"))
      (node (ref "U2") (pin "28") (pinfunction "GND_28") (pintype "passive"))
      (node (ref "U2") (pin "41") (pinfunction "GND_41") (pintype "passive"))
      (node (ref "U2") (pin "46") (pinfunction "GNDQ_46") (pintype "passive"))
      (node (ref "U2") (pin "52") (pinfunction "GNDQ_52") (pintype "passive"))
      (node (ref "U2") (pin "54") (pinfunction "GND_54") (pintype "passive"))
      (node (ref "U2") (pin "6") (pinfunction "GNDQ_6") (pintype "passive"))
      (node (ref "U3") (pin "4") (pinfunction "GND_4") (pintype "passive"))
      (node (ref "U4") (pin "2") (pinfunction "GND_2") (pintype "passive"))
      (node (ref "U5") (pin "12") (pinfunction "GND_12") (pintype "power_in"))
      (node (ref "U5") (pin "27") (pinfunction "BUSY_27") (pintype "input"))
      (node (ref "U6") (pin "15") (pinfunction "~{EN}_15") (pintype "passive"))
      (node (ref "U6") (pin "8") (pinfunction "GND_8") (pintype "passive"))
      (node (ref "U7") (pin "2") (pinfunction "GND_2") (pintype "passive"))
      (node (ref "X1") (pin "2") (pinfunction "2_2") (pintype "passive"))
      (node (ref "X1") (pin "4") (pinfunction "4_4") (pintype "passive"))
      (node (ref "X3") (pin "2") (pinfunction "2_2") (pintype "passive"))
      (node (ref "X3") (pin "4") (pinfunction "4_4") (pintype "passive"))
    )
    (net (code "162") (name "Net-(D1-PadA)") (class "Default")
      (node (ref "D1") (pin "A") (pinfunction "A_A") (pintype "passive"))
      (node (ref "R5") (pin "1") (pinfunction "1_1") (pintype "passive"))
    )
    (net (code "163") (name "Net-(D2-PadA)") (class "Default")
      (node (ref "D2") (pin "A") (pinfunction "A_A") (pintype "passive"))
      (node (ref "R38") (pin "2") (pinfunction "2_2") (pintype "passive"))
    )
    (net (code "164") (name "Net-(U1-ADC_REXT)") (class "Default")
      (node (ref "R17") (pin "2") (pinfunction "2_2") (pintype "passive"))
      (node (ref "U1") (pin "81") (pinfunction "ADC_REXT_81") (pintype "passive"))
    )
    (net (code "165") (name "Net-(U1-OTG_REXT)") (class "Default")
      (node (ref "R4") (pin "2") (pinfunction "2_2") (pintype "passive"))
      (node (ref "U1") (pin "159") (pinfunction "OTG_REXT_159") (pintype "passive"))
    )
    (net (code "166") (name "Net-(U1-USB_REXT)") (class "Default")
      (node (ref "R3") (pin "2") (pinfunction "2_2") (pintype "passive"))
      (node (ref "U1") (pin "167") (pinfunction "USB_REXT_167") (pintype "passive"))
    )
    (net (code "167") (name "Net-(U4-EN)") (class "Default")
      (node (ref "R34") (pin "2") (pinfunction "2_2") (pintype "passive"))
      (node (ref "U4") (pin "1") (pinfunction "EN_1") (pintype "passive"))
    )
    (net (code "168") (name "Net-(U4-FB)") (class "Default")
      (node (ref "R31") (pin "1") (pinfunction "1_1") (pintype "passive"))
      (node (ref "R33") (pin "2") (pinfunction "2_2") (pintype "passive"))
      (node (ref "U4") (pin "5") (pinfunction "FB_5") (pintype "passive"))
    )
    (net (code "169") (name "Net-(U4-LX)") (class "Default")
      (node (ref "L2") (pin "1") (pinfunction "1_1") (pintype "passive"))
      (node (ref "U4") (pin "3") (pinfunction "LX_3") (pintype "passive"))
    )
    (net (code "170") (name "Net-(U5-RSTI)") (class "Default")
      (node (ref "C49") (pin "1") (pinfunction "1_1") (pintype "passive"))
      (node (ref "R30") (pin "1") (pinfunction "1_1") (pintype "passive"))
      (node (ref "U5") (pin "2") (pinfunction "RSTI_2") (pintype "passive"))
    )
    (net (code "171") (name "Net-(U5-XI)") (class "Default")
      (node (ref "C55") (pin "2") (pinfunction "2_2") (pintype "passive"))
      (node (ref "U5") (pin "13") (pinfunction "XI_13") (pintype "passive"))
      (node (ref "X3") (pin "1") (pinfunction "1_1") (pintype "passive"))
    )
    (net (code "172") (name "Net-(U5-XO)") (class "Default")
      (node (ref "C54") (pin "2") (pinfunction "2_2") (pintype "passive"))
      (node (ref "U5") (pin "14") (pinfunction "XO_14") (pintype "output"))
      (node (ref "X3") (pin "3") (pinfunction "3_3") (pintype "passive"))
    )
    (net (code "173") (name "Net-(U7-EN)") (class "Default")
      (node (ref "R37") (pin "2") (pinfunction "2_2") (pintype "passive"))
      (node (ref "U7") (pin "1") (pinfunction "EN_1") (pintype "passive"))
    )
    (net (code "174") (name "Net-(U7-FB)") (class "Default")
      (node (ref "R35") (pin "1") (pinfunction "1_1") (pintype "passive"))
      (node (ref "R36") (pin "2") (pinfunction "2_2") (pintype "passive"))
      (node (ref "U7") (pin "5") (pinfunction "FB_5") (pintype "passive"))
    )
    (net (code "175") (name "Net-(U7-LX)") (class "Default")
      (node (ref "L3") (pin "1") (pinfunction "1_1") (pintype "passive"))
      (node (ref "U7") (pin "3") (pinfunction "LX_3") (pintype "passive"))
    )
    (net (code "176") (name "unconnected-(J1-CC1-PadA5)") (class "Default")
      (node (ref "J1") (pin "A5") (pinfunction "CC1_A5") (pintype "passive"))
    )
    (net (code "177") (name "unconnected-(J1-CC2-PadB5)") (class "Default")
      (node (ref "J1") (pin "B5") (pinfunction "CC2_B5") (pintype "passive"))
    )
    (net (code "178") (name "unconnected-(J1-SBU1-PadA8)") (class "Default")
      (node (ref "J1") (pin "A8") (pinfunction "SBU1_A8") (pintype "passive"))
    )
    (net (code "179") (name "unconnected-(J1-SBU2-PadB8)") (class "Default")
      (node (ref "J1") (pin "B8") (pinfunction "SBU2_B8") (pintype "passive"))
    )
    (net (code "180") (name "unconnected-(R6-Pad1)") (class "Default")
      (node (ref "R6") (pin "1") (pinfunction "1_1") (pintype "passive"))
    )
    (net (code "181") (name "unconnected-(R6-Pad8)") (class "Default")
      (node (ref "R6") (pin "8") (pinfunction "8_8") (pintype "passive"))
    )
    (net (code "182") (name "unconnected-(R7-Pad4)") (class "Default")
      (node (ref "R7") (pin "4") (pinfunction "4_4") (pintype "passive"))
    )
    (net (code "183") (name "unconnected-(R7-Pad5)") (class "Default")
      (node (ref "R7") (pin "5") (pinfunction "5_5") (pintype "passive"))
    )
    (net (code "184") (name "unconnected-(S1-Pad1)") (class "Default")
      (node (ref "S1") (pin "1") (pinfunction "1_1") (pintype "passive"))
    )
    (net (code "185") (name "unconnected-(U2-NC-Pad40)") (class "Default")
      (node (ref "U2") (pin "40") (pinfunction "NC_40") (pintype "passive"))
    )
    (net (code "186") (name "unconnected-(U5-ACK#-Pad7)") (class "Default")
      (node (ref "U5") (pin "7") (pinfunction "ACK#_7") (pintype "passive"))
    )
    (net (code "187") (name "unconnected-(U5-ACT#-Pad1)") (class "Default")
      (node (ref "U5") (pin "1") (pinfunction "ACT#_1") (pintype "output"))
    )
    (net (code "188") (name "unconnected-(U5-AFD#-Pad4)") (class "Default")
      (node (ref "U5") (pin "4") (pinfunction "AFD#_4") (pintype "output"))
    )
    (net (code "189") (name "unconnected-(U5-D1-Pad16)") (class "Default")
      (node (ref "U5") (pin "16") (pinfunction "D1_16") (pintype "bidirectional"))
    )
    (net (code "190") (name "unconnected-(U5-D2-Pad17)") (class "Default")
      (node (ref "U5") (pin "17") (pinfunction "D2_17") (pintype "bidirectional"))
    )
    (net (code "191") (name "unconnected-(U5-D4-Pad19)") (class "Default")
      (node (ref "U5") (pin "19") (pinfunction "D4_19") (pintype "bidirectional"))
    )
    (net (code "192") (name "unconnected-(U5-D6-Pad21)") (class "Default")
      (node (ref "U5") (pin "21") (pinfunction "D6_21") (pintype "bidirectional"))
    )
    (net (code "193") (name "unconnected-(U5-INI#-Pad26)") (class "Default")
      (node (ref "U5") (pin "26") (pinfunction "INI#_26") (pintype "output"))
    )
    (net (code "194") (name "unconnected-(U5-SCL-Pad24)") (class "Default")
      (node (ref "U5") (pin "24") (pinfunction "SCL_24") (pintype "output"))
    )
    (net (code "195") (name "unconnected-(U5-SIN#-Pad3)") (class "Default")
      (node (ref "U5") (pin "3") (pinfunction "SIN#_3") (pintype "output"))
    )
    (net (code "196") (name "unconnected-(U5-SLCT-Pad8)") (class "Default")
      (node (ref "U5") (pin "8") (pinfunction "SLCT_8") (pintype "passive"))
    )
    (net (code "197") (name "unconnected-(U5-STB#-Pad25)") (class "Default")
      (node (ref "U5") (pin "25") (pinfunction "STB#_25") (pintype "output"))
    )
  )
)
